# LoadSwitch.net
KiCad netlist of a schematic drawn in EAGLE
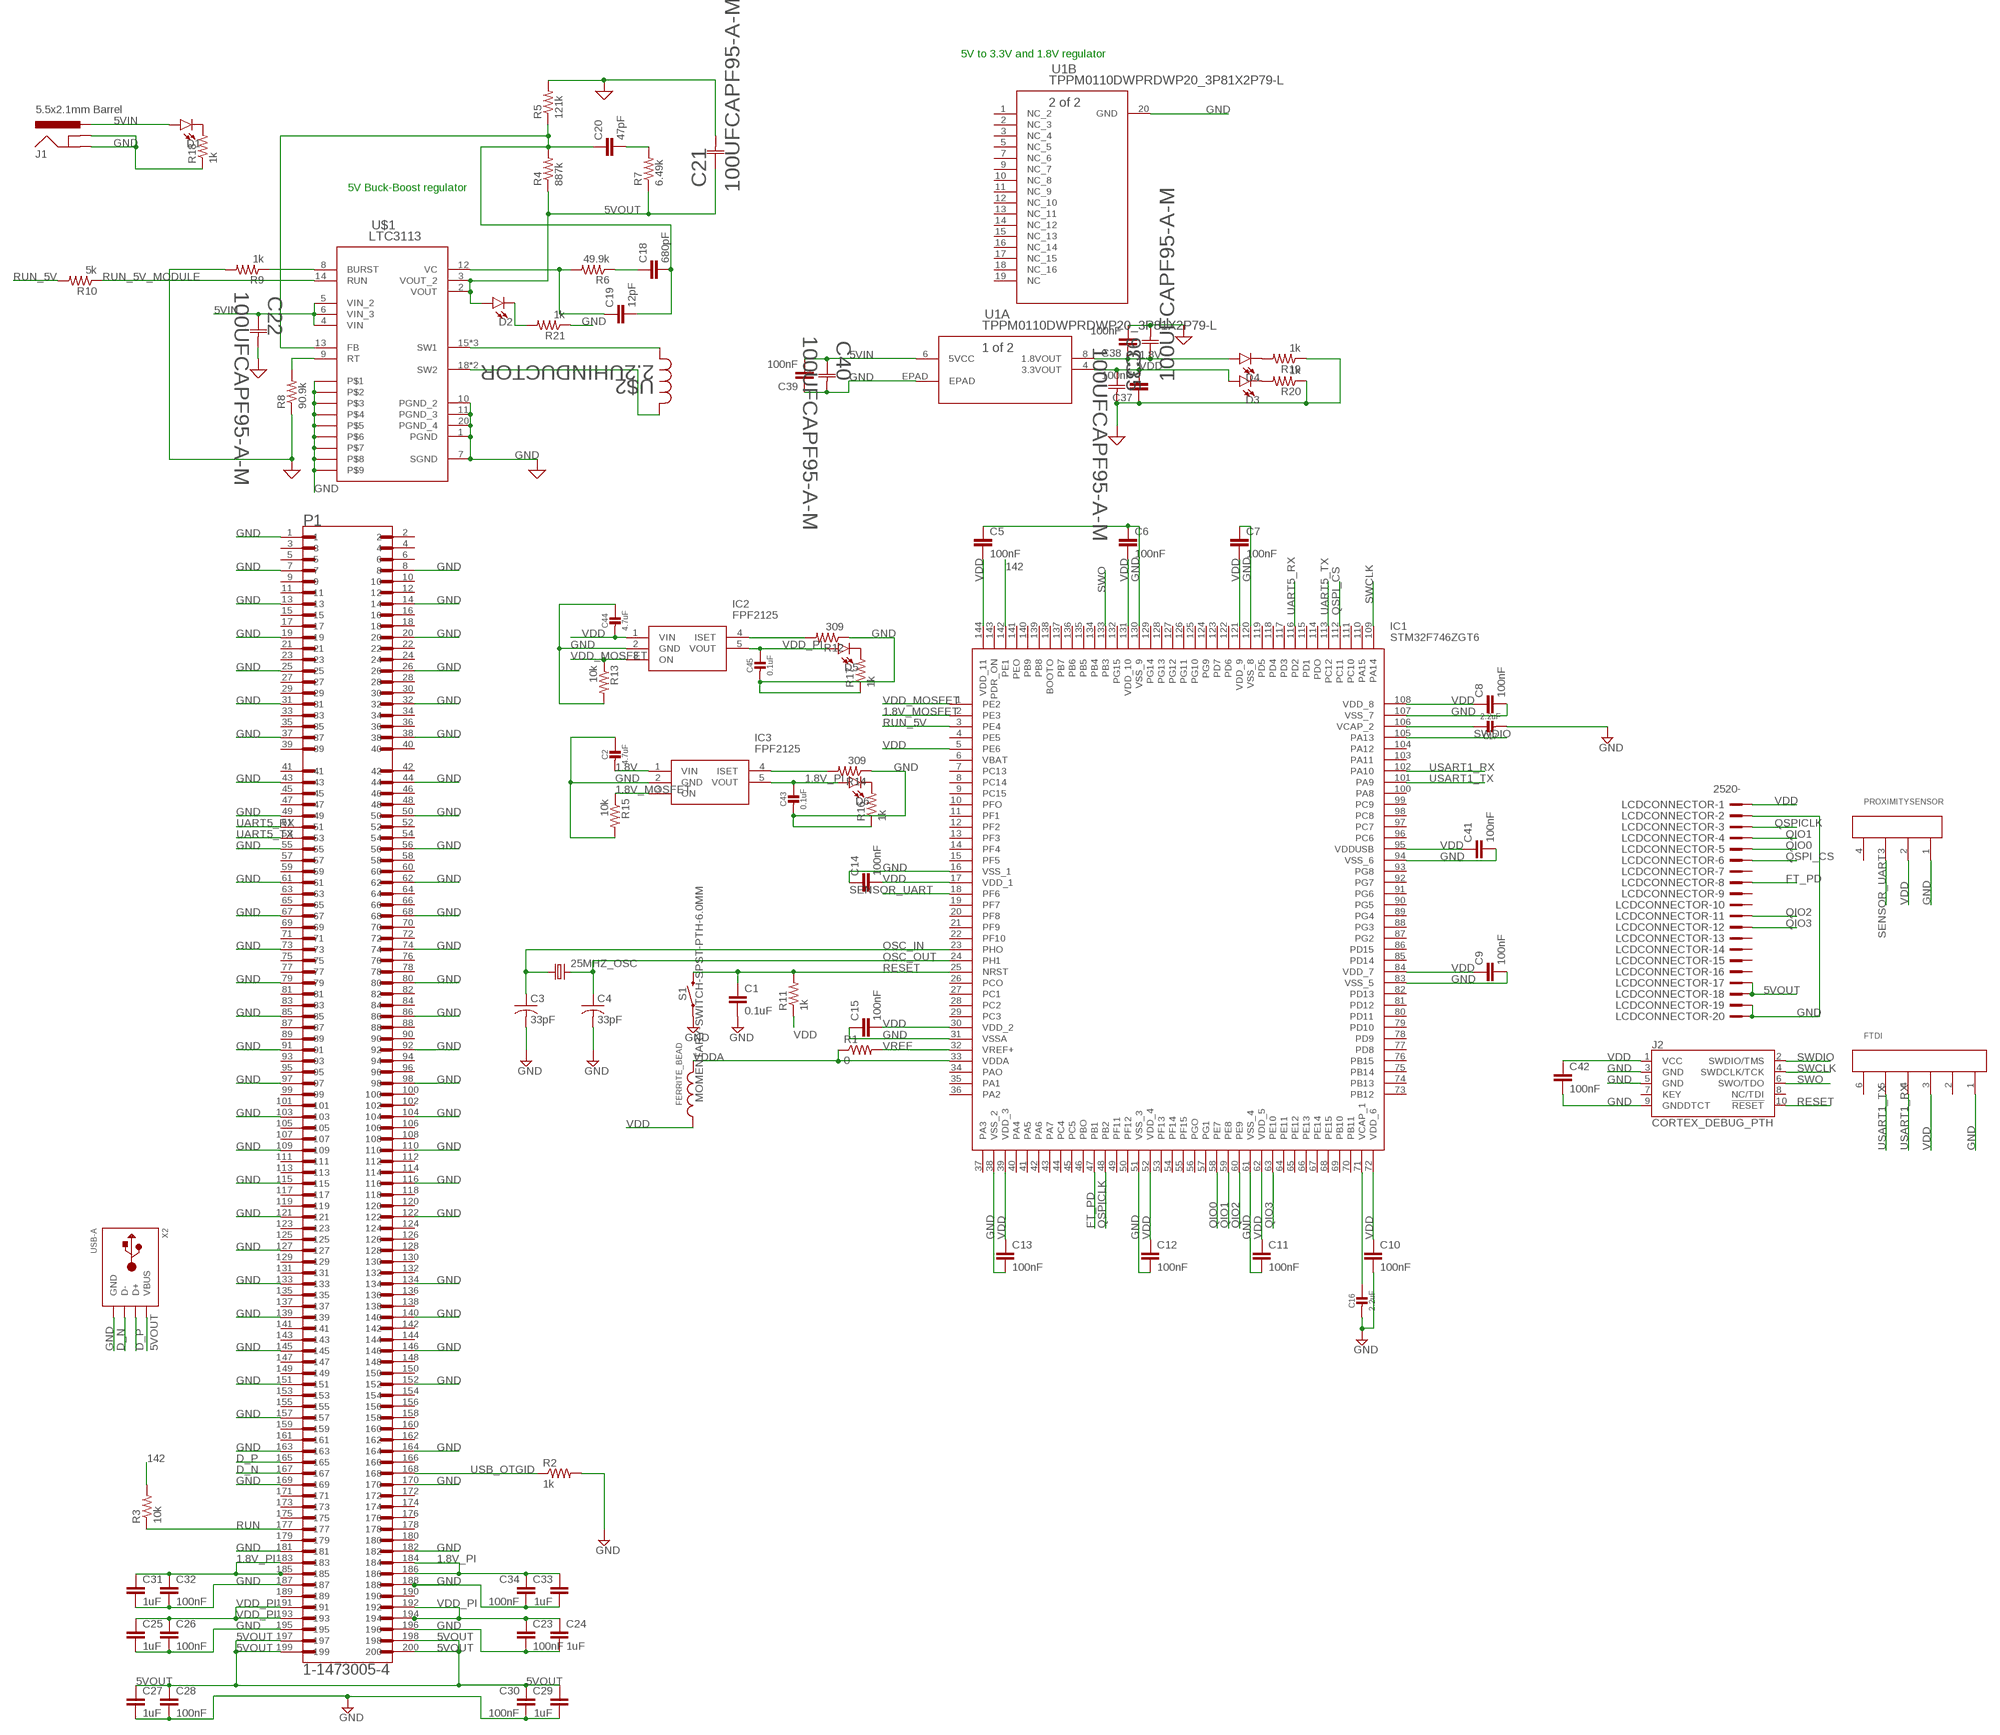
[diagram p0: schematic, sheet 1]

(export (version "E")
  (design (tool "Eeschema 10.0.6"))
  (components
    (comp (ref "25MHZ_OSC")
      (value "CRYSTALHC49UP")
      (footprint "eagle-import:HC49UP")
      (libsource (lib "eagle-import") (part "CRYSTALHC49UP"))
    )
    (comp (ref "C1")
      (value "0.1uF")
      (footprint "eagle-import:C0805")
      (libsource (lib "eagle-import") (part "C-EUC0805"))
    )
    (comp (ref "C2")
      (value "4.7uF")
      (footprint "eagle-import:0805-NO")
      (libsource (lib "eagle-import") (part "CAP_CERAMIC0805-NOOUTLINE"))
    )
    (comp (ref "C3")
      (value "33pF")
      (footprint "eagle-import:C0805")
      (libsource (lib "eagle-import") (part "C-USC0805"))
    )
    (comp (ref "C4")
      (value "33pF")
      (footprint "eagle-import:C0805")
      (libsource (lib "eagle-import") (part "C-USC0805"))
    )
    (comp (ref "C5")
      (value "100nF")
      (footprint "eagle-import:C0805")
      (libsource (lib "eagle-import") (part "C-EUC0805"))
    )
    (comp (ref "C6")
      (value "100nF")
      (footprint "eagle-import:C0805")
      (libsource (lib "eagle-import") (part "C-EUC0805"))
    )
    (comp (ref "C7")
      (value "100nF")
      (footprint "eagle-import:C0805")
      (libsource (lib "eagle-import") (part "C-EUC0805"))
    )
    (comp (ref "C8")
      (value "100nF")
      (footprint "eagle-import:C0805")
      (libsource (lib "eagle-import") (part "C-EUC0805"))
    )
    (comp (ref "C9")
      (value "100nF")
      (footprint "eagle-import:C0805")
      (libsource (lib "eagle-import") (part "C-EUC0805"))
    )
    (comp (ref "C10")
      (value "100nF")
      (footprint "eagle-import:C0805")
      (libsource (lib "eagle-import") (part "C-EUC0805"))
    )
    (comp (ref "C11")
      (value "100nF")
      (footprint "eagle-import:C0805")
      (libsource (lib "eagle-import") (part "C-EUC0805"))
    )
    (comp (ref "C12")
      (value "100nF")
      (footprint "eagle-import:C0805")
      (libsource (lib "eagle-import") (part "C-EUC0805"))
    )
    (comp (ref "C13")
      (value "100nF")
      (footprint "eagle-import:C0805")
      (libsource (lib "eagle-import") (part "C-EUC0805"))
    )
    (comp (ref "C14")
      (value "100nF")
      (footprint "eagle-import:C0805")
      (libsource (lib "eagle-import") (part "C-EUC0805"))
    )
    (comp (ref "C15")
      (value "100nF")
      (footprint "eagle-import:C0805")
      (libsource (lib "eagle-import") (part "C-EUC0805"))
    )
    (comp (ref "C16")
      (value "2.2uF")
      (footprint "eagle-import:0805-NO")
      (libsource (lib "eagle-import") (part "audio amplifier example_970892_CAP_CERAMIC0805-NOOUTLINE"))
    )
    (comp (ref "C17")
      (value "2.2uF")
      (footprint "eagle-import:0805-NO")
      (libsource (lib "eagle-import") (part "audio amplifier example_970892_CAP_CERAMIC0805-NOOUTLINE"))
    )
    (comp (ref "C18")
      (value "680pF")
      (footprint "eagle-import:C0805")
      (libsource (lib "eagle-import") (part "C-EUC0805"))
    )
    (comp (ref "C19")
      (value "12pF")
      (footprint "eagle-import:C0805")
      (libsource (lib "eagle-import") (part "C-EUC0805"))
    )
    (comp (ref "C20")
      (value "47pF")
      (footprint "eagle-import:C0805")
      (libsource (lib "eagle-import") (part "C-EUC0805"))
    )
    (comp (ref "C21")
      (value "100UFCAPF95-A-M")
      (footprint "eagle-import:F95-A-M")
      (fields (field (name "MANUFACTURER_PART_NUMBER") "F951A107KAAAQ2"))
      (libsource (lib "eagle-import") (part "100UFCAPF95-A-M"))
    )
    (comp (ref "C22")
      (value "100UFCAPF95-A-M")
      (footprint "eagle-import:F95-A-M")
      (fields (field (name "MANUFACTURER_PART_NUMBER") "F951A107KAAAQ2"))
      (libsource (lib "eagle-import") (part "100UFCAPF95-A-M"))
    )
    (comp (ref "C23")
      (value "100nF")
      (footprint "eagle-import:C0805")
      (libsource (lib "eagle-import") (part "C-EUC0805"))
    )
    (comp (ref "C24")
      (value "1uF")
      (footprint "eagle-import:C0805")
      (libsource (lib "eagle-import") (part "C-EUC0805"))
    )
    (comp (ref "C25")
      (value "1uF")
      (footprint "eagle-import:C0805")
      (libsource (lib "eagle-import") (part "C-EUC0805"))
    )
    (comp (ref "C26")
      (value "100nF")
      (footprint "eagle-import:C0805")
      (libsource (lib "eagle-import") (part "C-EUC0805"))
    )
    (comp (ref "C27")
      (value "1uF")
      (footprint "eagle-import:C0805")
      (libsource (lib "eagle-import") (part "C-EUC0805"))
    )
    (comp (ref "C28")
      (value "100nF")
      (footprint "eagle-import:C0805")
      (libsource (lib "eagle-import") (part "C-EUC0805"))
    )
    (comp (ref "C29")
      (value "1uF")
      (footprint "eagle-import:C0805")
      (libsource (lib "eagle-import") (part "C-EUC0805"))
    )
    (comp (ref "C30")
      (value "100nF")
      (footprint "eagle-import:C0805")
      (libsource (lib "eagle-import") (part "C-EUC0805"))
    )
    (comp (ref "C31")
      (value "1uF")
      (footprint "eagle-import:C0805")
      (libsource (lib "eagle-import") (part "C-EUC0805"))
    )
    (comp (ref "C32")
      (value "100nF")
      (footprint "eagle-import:C0805")
      (libsource (lib "eagle-import") (part "C-EUC0805"))
    )
    (comp (ref "C33")
      (value "1uF")
      (footprint "eagle-import:C0805")
      (libsource (lib "eagle-import") (part "C-EUC0805"))
    )
    (comp (ref "C34")
      (value "100nF")
      (footprint "eagle-import:C0805")
      (libsource (lib "eagle-import") (part "C-EUC0805"))
    )
    (comp (ref "C35")
      (value "100UFCAPF95-A-M")
      (footprint "eagle-import:F95-A-M")
      (fields (field (name "MANUFACTURER_PART_NUMBER") "F951A107KAAAQ2"))
      (libsource (lib "eagle-import") (part "100UFCAPF95-A-M"))
    )
    (comp (ref "C36")
      (value "100UFCAPF95-A-M")
      (footprint "eagle-import:F95-A-M")
      (fields (field (name "MANUFACTURER_PART_NUMBER") "F951A107KAAAQ2"))
      (libsource (lib "eagle-import") (part "100UFCAPF95-A-M"))
    )
    (comp (ref "C37")
      (value "100nF")
      (footprint "eagle-import:C0805")
      (libsource (lib "eagle-import") (part "C-EUC0805"))
    )
    (comp (ref "C38")
      (value "100nF")
      (footprint "eagle-import:C0805")
      (libsource (lib "eagle-import") (part "C-EUC0805"))
    )
    (comp (ref "C39")
      (value "100nF")
      (footprint "eagle-import:C0805")
      (libsource (lib "eagle-import") (part "C-EUC0805"))
    )
    (comp (ref "C40")
      (value "100UFCAPF95-A-M")
      (footprint "eagle-import:F95-A-M")
      (fields (field (name "MANUFACTURER_PART_NUMBER") "F951A107KAAAQ2"))
      (libsource (lib "eagle-import") (part "100UFCAPF95-A-M"))
    )
    (comp (ref "C41")
      (value "100nF")
      (footprint "eagle-import:C0805")
      (libsource (lib "eagle-import") (part "C-EUC0805"))
    )
    (comp (ref "C42")
      (value "100nF")
      (footprint "eagle-import:C0805")
      (libsource (lib "eagle-import") (part "C-EUC0805"))
    )
    (comp (ref "C43")
      (value "0.1uF")
      (footprint "eagle-import:0805-NO")
      (libsource (lib "eagle-import") (part "CAP_CERAMIC0805-NOOUTLINE"))
    )
    (comp (ref "C44")
      (value "4.7uF")
      (footprint "eagle-import:0805-NO")
      (libsource (lib "eagle-import") (part "CAP_CERAMIC0805-NOOUTLINE"))
    )
    (comp (ref "C45")
      (value "0.1uF")
      (footprint "eagle-import:0805-NO")
      (libsource (lib "eagle-import") (part "CAP_CERAMIC0805-NOOUTLINE"))
    )
    (comp (ref "D1")
      (value "LED0603")
      (footprint "eagle-import:LED-0603")
      (libsource (lib "eagle-import") (part "LED0603"))
    )
    (comp (ref "D2")
      (value "LED0603")
      (footprint "eagle-import:LED-0603")
      (libsource (lib "eagle-import") (part "LED0603"))
    )
    (comp (ref "D3")
      (value "LED0603")
      (footprint "eagle-import:LED-0603")
      (libsource (lib "eagle-import") (part "LED0603"))
    )
    (comp (ref "D4")
      (value "LED0603")
      (footprint "eagle-import:LED-0603")
      (libsource (lib "eagle-import") (part "LED0603"))
    )
    (comp (ref "D5")
      (value "LED0603")
      (footprint "eagle-import:LED-0603")
      (libsource (lib "eagle-import") (part "LED0603"))
    )
    (comp (ref "D6")
      (value "LED0603")
      (footprint "eagle-import:LED-0603")
      (libsource (lib "eagle-import") (part "LED0603"))
    )
    (comp (ref "FERRITE_BEAD")
      (value "WE-CBA_0805_782853112_HC")
      (footprint "eagle-import:WE-CBA_0805(W=4)")
      (libsource (lib "eagle-import") (part "WE-CBA_0805_HC_782853112"))
    )
    (comp (ref "FTDI")
      (value "66100611622")
      (footprint "eagle-import:66100611622")
      (libsource (lib "eagle-import") (part "66100611622"))
    )
    (comp (ref "IC1")
      (value "STM32F746ZGT6")
      (footprint "eagle-import:QFP50P2200X2200X160-144N")
      (fields
        (field (name "MOUSER_PART_NUMBER") "511-STM32F746ZGT6")
        (field (name "RS_PART_NUMBER") "8820290")
      )
      (libsource (lib "eagle-import") (part "STM32F746ZGT6"))
    )
    (comp (ref "IC2")
      (value "FPF2125")
      (footprint "eagle-import:SOT95P280X140-5N")
      (fields (field (name "MOUSER_PART_NUMBER") "512-FPF2125") (field (name "RS_PART_NUMBER") "7390195"))
      (libsource (lib "eagle-import") (part "FPF2125"))
    )
    (comp (ref "IC3")
      (value "FPF2125")
      (footprint "eagle-import:SOT95P280X140-5N")
      (fields (field (name "MOUSER_PART_NUMBER") "512-FPF2125") (field (name "RS_PART_NUMBER") "7390195"))
      (libsource (lib "eagle-import") (part "FPF2125"))
    )
    (comp (ref "J1")
      (value "5.5x2.1mm Barrel")
      (footprint "eagle-import:POWER_JACK_SMD")
      (libsource (lib "eagle-import") (part "POWER_JACKSMD"))
    )
    (comp (ref "J2")
      (value "CORTEX_DEBUG_PTH")
      (footprint "eagle-import:2X5-PTH-1.27MM")
      (libsource (lib "eagle-import") (part "CORTEX_DEBUG_PTH"))
    )
    (comp (ref "LCDCONNECTOR")
      (value "2520-")
      (footprint "eagle-import:PAK100_2500-20")
      (libsource (lib "eagle-import") (part "2520-"))
    )
    (comp (ref "P1")
      (value "1-1473005-4")
      (footprint "eagle-import:TE_1-1473005-4")
      (fields (field (name "MF") "TE Connectivity"))
      (libsource (lib "eagle-import") (part "1-1473005-4"))
    )
    (comp (ref "PROXIMITYSENSOR")
      (value "66100411622")
      (footprint "eagle-import:66100411622")
      (libsource (lib "eagle-import") (part "66100411622"))
    )
    (comp (ref "R1")
      (value "0")
      (footprint "eagle-import:R0805")
      (libsource (lib "eagle-import") (part "R-US_R0805"))
    )
    (comp (ref "R2")
      (value "1k")
      (footprint "eagle-import:R0805")
      (libsource (lib "eagle-import") (part "R-US_R0805"))
    )
    (comp (ref "R3")
      (value "10k")
      (footprint "eagle-import:R0805")
      (libsource (lib "eagle-import") (part "R-US_R0805"))
    )
    (comp (ref "R4")
      (value "887k")
      (footprint "eagle-import:R0805")
      (libsource (lib "eagle-import") (part "resistor_348_R-US_R0805"))
    )
    (comp (ref "R5")
      (value "121k")
      (footprint "eagle-import:R0805")
      (libsource (lib "eagle-import") (part "resistor_348_R-US_R0805"))
    )
    (comp (ref "R6")
      (value "49.9k")
      (footprint "eagle-import:R0805")
      (libsource (lib "eagle-import") (part "resistor_348_R-US_R0805"))
    )
    (comp (ref "R7")
      (value "6.49k")
      (footprint "eagle-import:R0805")
      (libsource (lib "eagle-import") (part "resistor_348_R-US_R0805"))
    )
    (comp (ref "R8")
      (value "90.9k")
      (footprint "eagle-import:R0805")
      (libsource (lib "eagle-import") (part "resistor_348_R-US_R0805"))
    )
    (comp (ref "R9")
      (value "1k")
      (footprint "eagle-import:R0805")
      (libsource (lib "eagle-import") (part "resistor_348_R-US_R0805"))
    )
    (comp (ref "R10")
      (value "5k")
      (footprint "eagle-import:R0805")
      (libsource (lib "eagle-import") (part "resistor_348_R-US_R0805"))
    )
    (comp (ref "R11")
      (value "1k")
      (footprint "eagle-import:R0805")
      (libsource (lib "eagle-import") (part "R-US_R0805"))
    )
    (comp (ref "R12")
      (value "309")
      (footprint "eagle-import:R0805")
      (libsource (lib "eagle-import") (part "R-US_R0805"))
    )
    (comp (ref "R13")
      (value "10k")
      (footprint "eagle-import:R0805")
      (libsource (lib "eagle-import") (part "R-US_R0805"))
    )
    (comp (ref "R14")
      (value "309")
      (footprint "eagle-import:R0805")
      (libsource (lib "eagle-import") (part "R-US_R0805"))
    )
    (comp (ref "R15")
      (value "10k")
      (footprint "eagle-import:R0805")
      (libsource (lib "eagle-import") (part "R-US_R0805"))
    )
    (comp (ref "R16")
      (value "1k")
      (footprint "eagle-import:R0805")
      (libsource (lib "eagle-import") (part "R-US_R0805"))
    )
    (comp (ref "R17")
      (value "1k")
      (footprint "eagle-import:R0805")
      (libsource (lib "eagle-import") (part "R-US_R0805"))
    )
    (comp (ref "R18")
      (value "1k")
      (footprint "eagle-import:R0805")
      (libsource (lib "eagle-import") (part "R-US_R0805"))
    )
    (comp (ref "R19")
      (value "1k")
      (footprint "eagle-import:R0805")
      (libsource (lib "eagle-import") (part "R-US_R0805"))
    )
    (comp (ref "R20")
      (value "1k")
      (footprint "eagle-import:R0805")
      (libsource (lib "eagle-import") (part "R-US_R0805"))
    )
    (comp (ref "R21")
      (value "1k")
      (footprint "eagle-import:R0805")
      (libsource (lib "eagle-import") (part "R-US_R0805"))
    )
    (comp (ref "S1")
      (value "MOMENTARY-SWITCH-SPST-PTH-6.0MM")
      (footprint "eagle-import:TACTILE_SWITCH_PTH_6.0MM")
      (libsource (lib "eagle-import") (part "MOMENTARY-SWITCH-SPST-PTH-6.0MM"))
    )
    (comp (ref "U$1")
      (value "LTC3113")
      (footprint "eagle-import:TSSOP-20_FE_CA")
      (libsource (lib "eagle-import") (part "LTC3113"))
    )
    (comp (ref "U$2")
      (value "2.2UHINDUCTOR")
      (footprint "eagle-import:IND_10040")
      (libsource (lib "eagle-import") (part "2.2UHINDUCTOR"))
    )
    (comp (ref "U1")
      (value "TPPM0110DWPRDWP20_3P81X2P79-L")
      (footprint "eagle-import:DWP20_3P81X2P79-L")
      (fields (field (name "MANUFACTURER_PART_NUMBER") "TPPM0110DWPR"))
      (libsource (lib "eagle-import") (part "TPPM0110DWPRDWP20_3P81X2P79-L"))
    )
    (comp (ref "X2")
      (value "USB-A")
      (footprint "eagle-import:MOLEX_480371000")
      (libsource (lib "eagle-import") (part "USB-A"))
    )
  )
  (nets
    (net (code "1") (name "/1.8V") (class "Default")
      (node (ref "C2") (pin "2") (pinfunction "2_2") (pintype "passive"))
      (node (ref "C36") (pin "1") (pinfunction "1_1") (pintype "passive"))
      (node (ref "C38") (pin "1") (pinfunction "1_1") (pintype "passive"))
      (node (ref "D4") (pin "A") (pinfunction "A_A") (pintype "passive"))
      (node (ref "IC3") (pin "1") (pinfunction "VIN_1") (pintype "input"))
      (node (ref "U1") (pin "8") (pinfunction "1.8VOUT_8") (pintype "output"))
    )
    (net (code "2") (name "/1.8V_MOSFET") (class "Default")
      (node (ref "IC1") (pin "2") (pinfunction "PE3_2") (pintype "bidirectional"))
      (node (ref "IC3") (pin "3") (pinfunction "ON_3") (pintype "input"))
      (node (ref "R15") (pin "1") (pinfunction "1_1") (pintype "passive"))
    )
    (net (code "3") (name "/1.8V_PI") (class "Default")
      (node (ref "C31") (pin "1") (pinfunction "1_1") (pintype "passive"))
      (node (ref "C32") (pin "1") (pinfunction "1_1") (pintype "passive"))
      (node (ref "C33") (pin "1") (pinfunction "1_1") (pintype "passive"))
      (node (ref "C34") (pin "1") (pinfunction "1_1") (pintype "passive"))
      (node (ref "C43") (pin "1") (pinfunction "1_1") (pintype "passive"))
      (node (ref "D6") (pin "A") (pinfunction "A_A") (pintype "passive"))
      (node (ref "IC3") (pin "5") (pinfunction "VOUT_5") (pintype "output"))
      (node (ref "P1") (pin "183") (pinfunction "183_183") (pintype "passive"))
      (node (ref "P1") (pin "184") (pinfunction "184_184") (pintype "passive"))
      (node (ref "P1") (pin "185") (pinfunction "185_185") (pintype "passive"))
      (node (ref "P1") (pin "186") (pinfunction "186_186") (pintype "passive"))
    )
    (net (code "4") (name "/5VIN") (class "Default")
      (node (ref "C22") (pin "1") (pinfunction "1_1") (pintype "passive"))
      (node (ref "C39") (pin "2") (pinfunction "2_2") (pintype "passive"))
      (node (ref "C40") (pin "1") (pinfunction "1_1") (pintype "passive"))
      (node (ref "D1") (pin "A") (pinfunction "A_A") (pintype "passive"))
      (node (ref "J1") (pin "VIN0") (pinfunction "PWR_VIN0") (pintype "bidirectional"))
      (node (ref "U$1") (pin "4") (pinfunction "VIN_4") (pintype "passive"))
      (node (ref "U$1") (pin "5") (pinfunction "VIN_2_5") (pintype "passive"))
      (node (ref "U$1") (pin "6") (pinfunction "VIN_3_6") (pintype "passive"))
      (node (ref "U1") (pin "6") (pinfunction "5VCC_6") (pintype "input"))
    )
    (net (code "5") (name "/5VOUT") (class "Default")
      (node (ref "C21") (pin "1") (pinfunction "1_1") (pintype "passive"))
      (node (ref "C27") (pin "1") (pinfunction "1_1") (pintype "passive"))
      (node (ref "C28") (pin "1") (pinfunction "1_1") (pintype "passive"))
      (node (ref "C29") (pin "1") (pinfunction "1_1") (pintype "passive"))
      (node (ref "C30") (pin "1") (pinfunction "1_1") (pintype "passive"))
      (node (ref "D2") (pin "A") (pinfunction "A_A") (pintype "passive"))
      (node (ref "LCDCONNECTOR") (pin "17") (pinfunction "KL_17") (pintype "passive"))
      (node (ref "LCDCONNECTOR") (pin "18") (pinfunction "KL_18") (pintype "passive"))
      (node (ref "P1") (pin "197") (pinfunction "197_197") (pintype "passive"))
      (node (ref "P1") (pin "198") (pinfunction "198_198") (pintype "passive"))
      (node (ref "P1") (pin "199") (pinfunction "199_199") (pintype "passive"))
      (node (ref "P1") (pin "200") (pinfunction "200_200") (pintype "passive"))
      (node (ref "R4") (pin "1") (pinfunction "1_1") (pintype "passive"))
      (node (ref "R7") (pin "1") (pinfunction "1_1") (pintype "passive"))
      (node (ref "U$1") (pin "2") (pinfunction "VOUT_2") (pintype "passive"))
      (node (ref "U$1") (pin "3") (pinfunction "VOUT_2_3") (pintype "passive"))
      (node (ref "X2") (pin "1") (pinfunction "VBUS_1") (pintype "power_in"))
    )
    (net (code "6") (name "/142") (class "Default")
      (node (ref "IC1") (pin "142") (pinfunction "PE1_142") (pintype "bidirectional"))
      (node (ref "R3") (pin "2") (pinfunction "2_2") (pintype "passive"))
    )
    (net (code "7") (name "/D_N") (class "Default")
      (node (ref "P1") (pin "167") (pinfunction "167_167") (pintype "passive"))
      (node (ref "X2") (pin "2") (pinfunction "D-_2") (pintype "bidirectional"))
    )
    (net (code "8") (name "/D_P") (class "Default")
      (node (ref "P1") (pin "165") (pinfunction "165_165") (pintype "passive"))
      (node (ref "X2") (pin "3") (pinfunction "D+_3") (pintype "bidirectional"))
    )
    (net (code "9") (name "/FT_PD") (class "Default")
      (node (ref "IC1") (pin "47") (pinfunction "PB1_47") (pintype "bidirectional"))
      (node (ref "LCDCONNECTOR") (pin "8") (pinfunction "KL_8") (pintype "passive"))
    )
    (net (code "10") (name "/OSC_IN") (class "Default")
      (node (ref "25MHZ_OSC") (pin "1") (pinfunction "1_1") (pintype "passive"))
      (node (ref "C3") (pin "1") (pinfunction "1_1") (pintype "passive"))
      (node (ref "IC1") (pin "23") (pinfunction "PHO_23") (pintype "bidirectional"))
    )
    (net (code "11") (name "/OSC_OUT") (class "Default")
      (node (ref "25MHZ_OSC") (pin "2") (pinfunction "2_2") (pintype "passive"))
      (node (ref "C4") (pin "1") (pinfunction "1_1") (pintype "passive"))
      (node (ref "IC1") (pin "24") (pinfunction "PH1_24") (pintype "bidirectional"))
    )
    (net (code "12") (name "/QIO0") (class "Default")
      (node (ref "IC1") (pin "58") (pinfunction "PE7_58") (pintype "bidirectional"))
      (node (ref "LCDCONNECTOR") (pin "5") (pinfunction "KL_5") (pintype "passive"))
    )
    (net (code "13") (name "/QIO1") (class "Default")
      (node (ref "IC1") (pin "59") (pinfunction "PE8_59") (pintype "bidirectional"))
      (node (ref "LCDCONNECTOR") (pin "4") (pinfunction "KL_4") (pintype "passive"))
    )
    (net (code "14") (name "/QIO2") (class "Default")
      (node (ref "IC1") (pin "60") (pinfunction "PE9_60") (pintype "bidirectional"))
      (node (ref "LCDCONNECTOR") (pin "11") (pinfunction "KL_11") (pintype "passive"))
    )
    (net (code "15") (name "/QIO3") (class "Default")
      (node (ref "IC1") (pin "63") (pinfunction "PE10_63") (pintype "bidirectional"))
      (node (ref "LCDCONNECTOR") (pin "12") (pinfunction "KL_12") (pintype "passive"))
    )
    (net (code "16") (name "/QSPICLK") (class "Default")
      (node (ref "IC1") (pin "48") (pinfunction "PB2_48") (pintype "bidirectional"))
      (node (ref "LCDCONNECTOR") (pin "3") (pinfunction "KL_3") (pintype "passive"))
    )
    (net (code "17") (name "/QSPI_CS") (class "Default")
      (node (ref "IC1") (pin "112") (pinfunction "PC11_112") (pintype "bidirectional"))
      (node (ref "LCDCONNECTOR") (pin "6") (pinfunction "KL_6") (pintype "passive"))
    )
    (net (code "18") (name "/RESET") (class "Default")
      (node (ref "C1") (pin "1") (pinfunction "1_1") (pintype "passive"))
      (node (ref "IC1") (pin "25") (pinfunction "NRST_25") (pintype "input"))
      (node (ref "J2") (pin "10") (pinfunction "~{RESET}_10") (pintype "bidirectional"))
      (node (ref "R11") (pin "2") (pinfunction "2_2") (pintype "passive"))
      (node (ref "S1") (pin "3") (pinfunction "2_3") (pintype "passive"))
    )
    (net (code "19") (name "/RUN") (class "Default")
      (node (ref "P1") (pin "177") (pinfunction "177_177") (pintype "passive"))
      (node (ref "R3") (pin "1") (pinfunction "1_1") (pintype "passive"))
    )
    (net (code "20") (name "/RUN_5V") (class "Default")
      (node (ref "IC1") (pin "3") (pinfunction "PE4_3") (pintype "bidirectional"))
      (node (ref "R10") (pin "2") (pinfunction "2_2") (pintype "passive"))
    )
    (net (code "21") (name "/RUN_5V_MODULE") (class "Default")
      (node (ref "R10") (pin "1") (pinfunction "1_1") (pintype "passive"))
      (node (ref "U$1") (pin "14") (pinfunction "RUN_14") (pintype "passive"))
    )
    (net (code "22") (name "/SENSOR_UART") (class "Default")
      (node (ref "IC1") (pin "18") (pinfunction "PF6_18") (pintype "bidirectional"))
      (node (ref "PROXIMITYSENSOR") (pin "3") (pinfunction "3_3") (pintype "passive"))
    )
    (net (code "23") (name "/SWCLK") (class "Default")
      (node (ref "IC1") (pin "109") (pinfunction "PA14_109") (pintype "bidirectional"))
      (node (ref "J2") (pin "4") (pinfunction "SWDCLK/TCK_4") (pintype "bidirectional"))
    )
    (net (code "24") (name "/SWDIO") (class "Default")
      (node (ref "IC1") (pin "105") (pinfunction "PA13_105") (pintype "bidirectional"))
      (node (ref "J2") (pin "2") (pinfunction "SWDIO/TMS_2") (pintype "bidirectional"))
    )
    (net (code "25") (name "/SWO") (class "Default")
      (node (ref "IC1") (pin "133") (pinfunction "PB3_133") (pintype "bidirectional"))
      (node (ref "J2") (pin "6") (pinfunction "SWO/TDO_6") (pintype "bidirectional"))
    )
    (net (code "26") (name "/UART5_RX") (class "Default")
      (node (ref "IC1") (pin "116") (pinfunction "PD2_116") (pintype "bidirectional"))
      (node (ref "P1") (pin "51") (pinfunction "51_51") (pintype "passive"))
    )
    (net (code "27") (name "/UART5_TX") (class "Default")
      (node (ref "IC1") (pin "113") (pinfunction "PC12_113") (pintype "bidirectional"))
      (node (ref "P1") (pin "53") (pinfunction "53_53") (pintype "passive"))
    )
    (net (code "28") (name "/USART1_RX") (class "Default")
      (node (ref "FTDI") (pin "4") (pinfunction "4_4") (pintype "passive"))
      (node (ref "IC1") (pin "102") (pinfunction "PA10_102") (pintype "bidirectional"))
    )
    (net (code "29") (name "/USART1_TX") (class "Default")
      (node (ref "FTDI") (pin "5") (pinfunction "5_5") (pintype "passive"))
      (node (ref "IC1") (pin "101") (pinfunction "PA9_101") (pintype "bidirectional"))
    )
    (net (code "30") (name "/USB_OTGID") (class "Default")
      (node (ref "P1") (pin "168") (pinfunction "168_168") (pintype "passive"))
      (node (ref "R2") (pin "1") (pinfunction "1_1") (pintype "passive"))
    )
    (net (code "31") (name "/VDD") (class "Default")
      (node (ref "C10") (pin "1") (pinfunction "1_1") (pintype "passive"))
      (node (ref "C11") (pin "1") (pinfunction "1_1") (pintype "passive"))
      (node (ref "C12") (pin "1") (pinfunction "1_1") (pintype "passive"))
      (node (ref "C13") (pin "1") (pinfunction "1_1") (pintype "passive"))
      (node (ref "C14") (pin "2") (pinfunction "2_2") (pintype "passive"))
      (node (ref "C15") (pin "2") (pinfunction "2_2") (pintype "passive"))
      (node (ref "C35") (pin "1") (pinfunction "1_1") (pintype "passive"))
      (node (ref "C37") (pin "2") (pinfunction "2_2") (pintype "passive"))
      (node (ref "C41") (pin "1") (pinfunction "1_1") (pintype "passive"))
      (node (ref "C42") (pin "1") (pinfunction "1_1") (pintype "passive"))
      (node (ref "C44") (pin "2") (pinfunction "2_2") (pintype "passive"))
      (node (ref "C5") (pin "2") (pinfunction "2_2") (pintype "passive"))
      (node (ref "C6") (pin "2") (pinfunction "2_2") (pintype "passive"))
      (node (ref "C7") (pin "2") (pinfunction "2_2") (pintype "passive"))
      (node (ref "C8") (pin "1") (pinfunction "1_1") (pintype "passive"))
      (node (ref "C9") (pin "1") (pinfunction "1_1") (pintype "passive"))
      (node (ref "D3") (pin "A") (pinfunction "A_A") (pintype "passive"))
      (node (ref "FERRITE_BEAD") (pin "1") (pinfunction "1_1") (pintype "passive"))
      (node (ref "FTDI") (pin "3") (pinfunction "3_3") (pintype "passive"))
      (node (ref "IC1") (pin "108") (pinfunction "VDD_8_108") (pintype "power_in"))
      (node (ref "IC1") (pin "121") (pinfunction "VDD_9_121") (pintype "power_in"))
      (node (ref "IC1") (pin "131") (pinfunction "VDD_10_131") (pintype "power_in"))
      (node (ref "IC1") (pin "144") (pinfunction "VDD_11_144") (pintype "power_in"))
      (node (ref "IC1") (pin "17") (pinfunction "VDD_1_17") (pintype "power_in"))
      (node (ref "IC1") (pin "30") (pinfunction "VDD_2_30") (pintype "power_in"))
      (node (ref "IC1") (pin "39") (pinfunction "VDD_3_39") (pintype "power_in"))
      (node (ref "IC1") (pin "5") (pinfunction "PE6_5") (pintype "bidirectional"))
      (node (ref "IC1") (pin "52") (pinfunction "VDD_4_52") (pintype "power_in"))
      (node (ref "IC1") (pin "62") (pinfunction "VDD_5_62") (pintype "power_in"))
      (node (ref "IC1") (pin "72") (pinfunction "VDD_6_72") (pintype "power_in"))
      (node (ref "IC1") (pin "84") (pinfunction "VDD_7_84") (pintype "power_in"))
      (node (ref "IC1") (pin "95") (pinfunction "VDDUSB_95") (pintype "power_in"))
      (node (ref "IC2") (pin "1") (pinfunction "VIN_1") (pintype "input"))
      (node (ref "J2") (pin "1") (pinfunction "VCC_1") (pintype "bidirectional"))
      (node (ref "LCDCONNECTOR") (pin "1") (pinfunction "KL_1") (pintype "passive"))
      (node (ref "PROXIMITYSENSOR") (pin "2") (pinfunction "2_2") (pintype "passive"))
      (node (ref "R11") (pin "1") (pinfunction "1_1") (pintype "passive"))
      (node (ref "U1") (pin "4") (pinfunction "3.3VOUT_4") (pintype "output"))
    )
    (net (code "32") (name "/VDDA") (class "Default")
      (node (ref "FERRITE_BEAD") (pin "2") (pinfunction "2_2") (pintype "passive"))
      (node (ref "IC1") (pin "33") (pinfunction "VDDA_33") (pintype "power_in"))
      (node (ref "R1") (pin "1") (pinfunction "1_1") (pintype "passive"))
    )
    (net (code "33") (name "/VDD_MOSFET") (class "Default")
      (node (ref "IC1") (pin "1") (pinfunction "PE2_1") (pintype "bidirectional"))
      (node (ref "IC2") (pin "3") (pinfunction "ON_3") (pintype "input"))
      (node (ref "R13") (pin "1") (pinfunction "1_1") (pintype "passive"))
    )
    (net (code "34") (name "/VDD_PI") (class "Default")
      (node (ref "C23") (pin "1") (pinfunction "1_1") (pintype "passive"))
      (node (ref "C24") (pin "1") (pinfunction "1_1") (pintype "passive"))
      (node (ref "C25") (pin "1") (pinfunction "1_1") (pintype "passive"))
      (node (ref "C26") (pin "1") (pinfunction "1_1") (pintype "passive"))
      (node (ref "C45") (pin "1") (pinfunction "1_1") (pintype "passive"))
      (node (ref "D5") (pin "A") (pinfunction "A_A") (pintype "passive"))
      (node (ref "IC2") (pin "5") (pinfunction "VOUT_5") (pintype "output"))
      (node (ref "P1") (pin "191") (pinfunction "191_191") (pintype "passive"))
      (node (ref "P1") (pin "192") (pinfunction "192_192") (pintype "passive"))
      (node (ref "P1") (pin "193") (pinfunction "193_193") (pintype "passive"))
      (node (ref "P1") (pin "194") (pinfunction "194_194") (pintype "passive"))
    )
    (net (code "35") (name "/VREF") (class "Default")
      (node (ref "IC1") (pin "32") (pinfunction "VREF+_32") (pintype "input"))
      (node (ref "R1") (pin "2") (pinfunction "2_2") (pintype "passive"))
    )
    (net (code "36") (name "GND") (class "Default")
      (node (ref "C1") (pin "2") (pinfunction "2_2") (pintype "passive"))
      (node (ref "C10") (pin "2") (pinfunction "2_2") (pintype "passive"))
      (node (ref "C11") (pin "2") (pinfunction "2_2") (pintype "passive"))
      (node (ref "C12") (pin "2") (pinfunction "2_2") (pintype "passive"))
      (node (ref "C13") (pin "2") (pinfunction "2_2") (pintype "passive"))
      (node (ref "C14") (pin "1") (pinfunction "1_1") (pintype "passive"))
      (node (ref "C15") (pin "1") (pinfunction "1_1") (pintype "passive"))
      (node (ref "C16") (pin "2") (pinfunction "2_2") (pintype "passive"))
      (node (ref "C17") (pin "2") (pinfunction "2_2") (pintype "passive"))
      (node (ref "C2") (pin "1") (pinfunction "1_1") (pintype "passive"))
      (node (ref "C21") (pin "2") (pinfunction "2_2") (pintype "passive"))
      (node (ref "C22") (pin "2") (pinfunction "2_2") (pintype "passive"))
      (node (ref "C23") (pin "2") (pinfunction "2_2") (pintype "passive"))
      (node (ref "C24") (pin "2") (pinfunction "2_2") (pintype "passive"))
      (node (ref "C25") (pin "2") (pinfunction "2_2") (pintype "passive"))
      (node (ref "C26") (pin "2") (pinfunction "2_2") (pintype "passive"))
      (node (ref "C27") (pin "2") (pinfunction "2_2") (pintype "passive"))
      (node (ref "C28") (pin "2") (pinfunction "2_2") (pintype "passive"))
      (node (ref "C29") (pin "2") (pinfunction "2_2") (pintype "passive"))
      (node (ref "C3") (pin "2") (pinfunction "2_2") (pintype "passive"))
      (node (ref "C30") (pin "2") (pinfunction "2_2") (pintype "passive"))
      (node (ref "C31") (pin "2") (pinfunction "2_2") (pintype "passive"))
      (node (ref "C32") (pin "2") (pinfunction "2_2") (pintype "passive"))
      (node (ref "C33") (pin "2") (pinfunction "2_2") (pintype "passive"))
      (node (ref "C34") (pin "2") (pinfunction "2_2") (pintype "passive"))
      (node (ref "C35") (pin "2") (pinfunction "2_2") (pintype "passive"))
      (node (ref "C36") (pin "2") (pinfunction "2_2") (pintype "passive"))
      (node (ref "C37") (pin "1") (pinfunction "1_1") (pintype "passive"))
      (node (ref "C38") (pin "2") (pinfunction "2_2") (pintype "passive"))
      (node (ref "C39") (pin "1") (pinfunction "1_1") (pintype "passive"))
      (node (ref "C4") (pin "2") (pinfunction "2_2") (pintype "passive"))
      (node (ref "C40") (pin "2") (pinfunction "2_2") (pintype "passive"))
      (node (ref "C41") (pin "2") (pinfunction "2_2") (pintype "passive"))
      (node (ref "C42") (pin "2") (pinfunction "2_2") (pintype "passive"))
      (node (ref "C43") (pin "2") (pinfunction "2_2") (pintype "passive"))
      (node (ref "C44") (pin "1") (pinfunction "1_1") (pintype "passive"))
      (node (ref "C45") (pin "2") (pinfunction "2_2") (pintype "passive"))
      (node (ref "C5") (pin "1") (pinfunction "1_1") (pintype "passive"))
      (node (ref "C6") (pin "1") (pinfunction "1_1") (pintype "passive"))
      (node (ref "C7") (pin "1") (pinfunction "1_1") (pintype "passive"))
      (node (ref "C8") (pin "2") (pinfunction "2_2") (pintype "passive"))
      (node (ref "C9") (pin "2") (pinfunction "2_2") (pintype "passive"))
      (node (ref "FTDI") (pin "1") (pinfunction "1_1") (pintype "passive"))
      (node (ref "IC1") (pin "107") (pinfunction "VSS_7_107") (pintype "power_in"))
      (node (ref "IC1") (pin "120") (pinfunction "VSS_8_120") (pintype "power_in"))
      (node (ref "IC1") (pin "130") (pinfunction "VSS_9_130") (pintype "power_in"))
      (node (ref "IC1") (pin "16") (pinfunction "VSS_1_16") (pintype "power_in"))
      (node (ref "IC1") (pin "31") (pinfunction "VSSA_31") (pintype "power_in"))
      (node (ref "IC1") (pin "38") (pinfunction "VSS_2_38") (pintype "power_in"))
      (node (ref "IC1") (pin "51") (pinfunction "VSS_3_51") (pintype "power_in"))
      (node (ref "IC1") (pin "61") (pinfunction "VSS_4_61") (pintype "power_in"))
      (node (ref "IC1") (pin "83") (pinfunction "VSS_5_83") (pintype "power_in"))
      (node (ref "IC1") (pin "94") (pinfunction "VSS_6_94") (pintype "power_in"))
      (node (ref "IC2") (pin "2") (pinfunction "GND_2") (pintype "power_in"))
      (node (ref "IC3") (pin "2") (pinfunction "GND_2") (pintype "power_in"))
      (node (ref "J1") (pin "GND") (pinfunction "GNDBREAK_GND") (pintype "bidirectional"))
      (node (ref "J1") (pin "P$4") (pinfunction "GND_P$4") (pintype "bidirectional"))
      (node (ref "J2") (pin "3") (pinfunction "GND_3") (pintype "bidirectional"))
      (node (ref "J2") (pin "5") (pinfunction "GND_5") (pintype "bidirectional"))
      (node (ref "J2") (pin "9") (pinfunction "GNDDTCT_9") (pintype "bidirectional"))
      (node (ref "LCDCONNECTOR") (pin "19") (pinfunction "KL_19") (pintype "passive"))
      (node (ref "LCDCONNECTOR") (pin "2") (pinfunction "KL_2") (pintype "passive"))
      (node (ref "LCDCONNECTOR") (pin "20") (pinfunction "KL_20") (pintype "passive"))
      (node (ref "P1") (pin "1") (pinfunction "1_1") (pintype "passive"))
      (node (ref "P1") (pin "103") (pinfunction "103_103") (pintype "passive"))
      (node (ref "P1") (pin "104") (pinfunction "104_104") (pintype "passive"))
      (node (ref "P1") (pin "109") (pinfunction "109_109") (pintype "passive"))
      (node (ref "P1") (pin "110") (pinfunction "110_110") (pintype "passive"))
      (node (ref "P1") (pin "115") (pinfunction "115_115") (pintype "passive"))
      (node (ref "P1") (pin "116") (pinfunction "116_116") (pintype "passive"))
      (node (ref "P1") (pin "121") (pinfunction "121_121") (pintype "passive"))
      (node (ref "P1") (pin "122") (pinfunction "122_122") (pintype "passive"))
      (node (ref "P1") (pin "127") (pinfunction "127_127") (pintype "passive"))
      (node (ref "P1") (pin "13") (pinfunction "13_13") (pintype "passive"))
      (node (ref "P1") (pin "133") (pinfunction "133_133") (pintype "passive"))
      (node (ref "P1") (pin "134") (pinfunction "134_134") (pintype "passive"))
      (node (ref "P1") (pin "139") (pinfunction "139_139") (pintype "passive"))
      (node (ref "P1") (pin "14") (pinfunction "14_14") (pintype "passive"))
      (node (ref "P1") (pin "140") (pinfunction "140_140") (pintype "passive"))
      (node (ref "P1") (pin "145") (pinfunction "145_145") (pintype "passive"))
      (node (ref "P1") (pin "146") (pinfunction "146_146") (pintype "passive"))
      (node (ref "P1") (pin "151") (pinfunction "151_151") (pintype "passive"))
      (node (ref "P1") (pin "152") (pinfunction "152_152") (pintype "passive"))
      (node (ref "P1") (pin "157") (pinfunction "157_157") (pintype "passive"))
      (node (ref "P1") (pin "163") (pinfunction "163_163") (pintype "passive"))
      (node (ref "P1") (pin "164") (pinfunction "164_164") (pintype "passive"))
      (node (ref "P1") (pin "169") (pinfunction "169_169") (pintype "passive"))
      (node (ref "P1") (pin "170") (pinfunction "170_170") (pintype "passive"))
      (node (ref "P1") (pin "181") (pinfunction "181_181") (pintype "passive"))
      (node (ref "P1") (pin "182") (pinfunction "182_182") (pintype "passive"))
      (node (ref "P1") (pin "187") (pinfunction "187_187") (pintype "passive"))
      (node (ref "P1") (pin "188") (pinfunction "188_188") (pintype "passive"))
      (node (ref "P1") (pin "19") (pinfunction "19_19") (pintype "passive"))
      (node (ref "P1") (pin "195") (pinfunction "195_195") (pintype "passive"))
      (node (ref "P1") (pin "196") (pinfunction "196_196") (pintype "passive"))
      (node (ref "P1") (pin "20") (pinfunction "20_20") (pintype "passive"))
      (node (ref "P1") (pin "25") (pinfunction "25_25") (pintype "passive"))
      (node (ref "P1") (pin "26") (pinfunction "26_26") (pintype "passive"))
      (node (ref "P1") (pin "31") (pinfunction "31_31") (pintype "passive"))
      (node (ref "P1") (pin "32") (pinfunction "32_32") (pintype "passive"))
      (node (ref "P1") (pin "37") (pinfunction "37_37") (pintype "passive"))
      (node (ref "P1") (pin "38") (pinfunction "38_38") (pintype "passive"))
      (node (ref "P1") (pin "43") (pinfunction "43_43") (pintype "passive"))
      (node (ref "P1") (pin "44") (pinfunction "44_44") (pintype "passive"))
      (node (ref "P1") (pin "49") (pinfunction "49_49") (pintype "passive"))
      (node (ref "P1") (pin "50") (pinfunction "50_50") (pintype "passive"))
      (node (ref "P1") (pin "55") (pinfunction "55_55") (pintype "passive"))
      (node (ref "P1") (pin "56") (pinfunction "56_56") (pintype "passive"))
      (node (ref "P1") (pin "61") (pinfunction "61_61") (pintype "passive"))
      (node (ref "P1") (pin "62") (pinfunction "62_62") (pintype "passive"))
      (node (ref "P1") (pin "67") (pinfunction "67_67") (pintype "passive"))
      (node (ref "P1") (pin "68") (pinfunction "68_68") (pintype "passive"))
      (node (ref "P1") (pin "7") (pinfunction "7_7") (pintype "passive"))
      (node (ref "P1") (pin "73") (pinfunction "73_73") (pintype "passive"))
      (node (ref "P1") (pin "74") (pinfunction "74_74") (pintype "passive"))
      (node (ref "P1") (pin "79") (pinfunction "79_79") (pintype "passive"))
      (node (ref "P1") (pin "8") (pinfunction "8_8") (pintype "passive"))
      (node (ref "P1") (pin "80") (pinfunction "80_80") (pintype "passive"))
      (node (ref "P1") (pin "85") (pinfunction "85_85") (pintype "passive"))
      (node (ref "P1") (pin "86") (pinfunction "86_86") (pintype "passive"))
      (node (ref "P1") (pin "91") (pinfunction "91_91") (pintype "passive"))
      (node (ref "P1") (pin "92") (pinfunction "92_92") (pintype "passive"))
      (node (ref "P1") (pin "97") (pinfunction "97_97") (pintype "passive"))
      (node (ref "P1") (pin "98") (pinfunction "98_98") (pintype "passive"))
      (node (ref "PROXIMITYSENSOR") (pin "1") (pinfunction "1_1") (pintype "passive"))
      (node (ref "R12") (pin "1") (pinfunction "1_1") (pintype "passive"))
      (node (ref "R13") (pin "2") (pinfunction "2_2") (pintype "passive"))
      (node (ref "R14") (pin "1") (pinfunction "1_1") (pintype "passive"))
      (node (ref "R15") (pin "2") (pinfunction "2_2") (pintype "passive"))
      (node (ref "R16") (pin "1") (pinfunction "1_1") (pintype "passive"))
      (node (ref "R17") (pin "1") (pinfunction "1_1") (pintype "passive"))
      (node (ref "R18") (pin "1") (pinfunction "1_1") (pintype "passive"))
      (node (ref "R19") (pin "1") (pinfunction "1_1") (pintype "passive"))
      (node (ref "R2") (pin "2") (pinfunction "2_2") (pintype "passive"))
      (node (ref "R20") (pin "1") (pinfunction "1_1") (pintype "passive"))
      (node (ref "R21") (pin "1") (pinfunction "1_1") (pintype "passive"))
      (node (ref "R5") (pin "2") (pinfunction "2_2") (pintype "passive"))
      (node (ref "R8") (pin "1") (pinfunction "1_1") (pintype "passive"))
      (node (ref "R9") (pin "2") (pinfunction "2_2") (pintype "passive"))
      (node (ref "S1") (pin "1") (pinfunction "1_1") (pintype "passive"))
      (node (ref "U$1") (pin "1") (pinfunction "PGND_1") (pintype "passive"))
      (node (ref "U$1") (pin "10") (pinfunction "PGND_2_10") (pintype "passive"))
      (node (ref "U$1") (pin "11") (pinfunction "PGND_3_11") (pintype "passive"))
      (node (ref "U$1") (pin "20") (pinfunction "PGND_4_20") (pintype "passive"))
      (node (ref "U$1") (pin "7") (pinfunction "SGND_7") (pintype "passive"))
      (node (ref "U$1") (pin "P$1") (pinfunction "P$1_P$1") (pintype "passive"))
      (node (ref "U$1") (pin "P$2") (pinfunction "P$2_P$2") (pintype "passive"))
      (node (ref "U$1") (pin "P$3") (pinfunction "P$3_P$3") (pintype "passive"))
      (node (ref "U$1") (pin "P$4") (pinfunction "P$4_P$4") (pintype "passive"))
      (node (ref "U$1") (pin "P$5") (pinfunction "P$5_P$5") (pintype "passive"))
      (node (ref "U$1") (pin "P$6") (pinfunction "P$6_P$6") (pintype "passive"))
      (node (ref "U$1") (pin "P$7") (pinfunction "P$7_P$7") (pintype "passive"))
      (node (ref "U$1") (pin "P$8") (pinfunction "P$8_P$8") (pintype "passive"))
      (node (ref "U$1") (pin "P$9") (pinfunction "P$9_P$9") (pintype "passive"))
      (node (ref "U1") (pin "20") (pinfunction "GND_20") (pintype "power_in"))
      (node (ref "U1") (pin "EPAD") (pinfunction "EPAD_EPAD") (pintype "passive"))
      (node (ref "X2") (pin "4") (pinfunction "GND_4") (pintype "power_in"))
    )
    (net (code "37") (name "Net-(C18-Pad1)") (class "Default")
      (node (ref "C18") (pin "1") (pinfunction "1_1") (pintype "passive"))
      (node (ref "R6") (pin "1") (pinfunction "1_1") (pintype "passive"))
    )
    (net (code "38") (name "Net-(C20-Pad2)") (class "Default")
      (node (ref "C20") (pin "2") (pinfunction "2_2") (pintype "passive"))
      (node (ref "R7") (pin "2") (pinfunction "2_2") (pintype "passive"))
    )
    (net (code "39") (name "Net-(D1-PadC)") (class "Default")
      (node (ref "D1") (pin "C") (pinfunction "C_C") (pintype "passive"))
      (node (ref "R18") (pin "2") (pinfunction "2_2") (pintype "passive"))
    )
    (net (code "40") (name "Net-(D2-PadC)") (class "Default")
      (node (ref "D2") (pin "C") (pinfunction "C_C") (pintype "passive"))
      (node (ref "R21") (pin "2") (pinfunction "2_2") (pintype "passive"))
    )
    (net (code "41") (name "Net-(D3-PadC)") (class "Default")
      (node (ref "D3") (pin "C") (pinfunction "C_C") (pintype "passive"))
      (node (ref "R20") (pin "2") (pinfunction "2_2") (pintype "passive"))
    )
    (net (code "42") (name "Net-(D4-PadC)") (class "Default")
      (node (ref "D4") (pin "C") (pinfunction "C_C") (pintype "passive"))
      (node (ref "R19") (pin "2") (pinfunction "2_2") (pintype "passive"))
    )
    (net (code "43") (name "Net-(D5-PadC)") (class "Default")
      (node (ref "D5") (pin "C") (pinfunction "C_C") (pintype "passive"))
      (node (ref "R17") (pin "2") (pinfunction "2_2") (pintype "passive"))
    )
    (net (code "44") (name "Net-(D6-PadC)") (class "Default")
      (node (ref "D6") (pin "C") (pinfunction "C_C") (pintype "passive"))
      (node (ref "R16") (pin "2") (pinfunction "2_2") (pintype "passive"))
    )
    (net (code "45") (name "Net-(IC1-VCAP_1)") (class "Default")
      (node (ref "C16") (pin "1") (pinfunction "1_1") (pintype "passive"))
      (node (ref "IC1") (pin "71") (pinfunction "VCAP_1_71") (pintype "bidirectional"))
    )
    (net (code "46") (name "Net-(IC1-VCAP_2)") (class "Default")
      (node (ref "C17") (pin "1") (pinfunction "1_1") (pintype "passive"))
      (node (ref "IC1") (pin "106") (pinfunction "VCAP_2_106") (pintype "bidirectional"))
    )
    (net (code "47") (name "Net-(IC2-ISET)") (class "Default")
      (node (ref "IC2") (pin "4") (pinfunction "ISET_4") (pintype "input"))
      (node (ref "R12") (pin "2") (pinfunction "2_2") (pintype "passive"))
    )
    (net (code "48") (name "Net-(IC3-ISET)") (class "Default")
      (node (ref "IC3") (pin "4") (pinfunction "ISET_4") (pintype "input"))
      (node (ref "R14") (pin "2") (pinfunction "2_2") (pintype "passive"))
    )
    (net (code "49") (name "Net-(U$1-BURST)") (class "Default")
      (node (ref "R9") (pin "1") (pinfunction "1_1") (pintype "passive"))
      (node (ref "U$1") (pin "8") (pinfunction "BURST_8") (pintype "passive"))
    )
    (net (code "50") (name "Net-(U$1-FB)") (class "Default")
      (node (ref "C18") (pin "2") (pinfunction "2_2") (pintype "passive"))
      (node (ref "C19") (pin "2") (pinfunction "2_2") (pintype "passive"))
      (node (ref "C20") (pin "1") (pinfunction "1_1") (pintype "passive"))
      (node (ref "R4") (pin "2") (pinfunction "2_2") (pintype "passive"))
      (node (ref "R5") (pin "1") (pinfunction "1_1") (pintype "passive"))
      (node (ref "U$1") (pin "13") (pinfunction "FB_13") (pintype "passive"))
    )
    (net (code "51") (name "Net-(U$1-RT)") (class "Default")
      (node (ref "R8") (pin "2") (pinfunction "2_2") (pintype "passive"))
      (node (ref "U$1") (pin "9") (pinfunction "RT_9") (pintype "passive"))
    )
    (net (code "52") (name "Net-(U$1-SW1-Pad15)") (class "Default")
      (node (ref "U$1") (pin "15") (pinfunction "SW1_15") (pintype "passive"))
      (node (ref "U$1") (pin "16") (pinfunction "SW1_16") (pintype "passive"))
      (node (ref "U$1") (pin "17") (pinfunction "SW1_17") (pintype "passive"))
      (node (ref "U$2") (pin "2") (pinfunction "2_2") (pintype "passive"))
    )
    (net (code "53") (name "Net-(U$1-SW2-Pad18)") (class "Default")
      (node (ref "U$1") (pin "18") (pinfunction "SW2_18") (pintype "passive"))
      (node (ref "U$1") (pin "19") (pinfunction "SW2_19") (pintype "passive"))
      (node (ref "U$2") (pin "1") (pinfunction "1_1") (pintype "passive"))
    )
    (net (code "54") (name "Net-(U$1-VC)") (class "Default")
      (node (ref "C19") (pin "1") (pinfunction "1_1") (pintype "passive"))
      (node (ref "R6") (pin "2") (pinfunction "2_2") (pintype "passive"))
      (node (ref "U$1") (pin "12") (pinfunction "VC_12") (pintype "passive"))
    )
    (net (code "55") (name "unconnected-(FTDI-Pad2)") (class "Default")
      (node (ref "FTDI") (pin "2") (pinfunction "2_2") (pintype "passive"))
    )
    (net (code "56") (name "unconnected-(FTDI-Pad6)") (class "Default")
      (node (ref "FTDI") (pin "6") (pinfunction "6_6") (pintype "passive"))
    )
    (net (code "57") (name "unconnected-(IC1-BOOTO-Pad138)") (class "Default")
      (node (ref "IC1") (pin "138") (pinfunction "BOOTO_138") (pintype "bidirectional"))
    )
    (net (code "58") (name "unconnected-(IC1-PA1-Pad35)") (class "Default")
      (node (ref "IC1") (pin "35") (pinfunction "PA1_35") (pintype "bidirectional"))
    )
    (net (code "59") (name "unconnected-(IC1-PA2-Pad36)") (class "Default")
      (node (ref "IC1") (pin "36") (pinfunction "PA2_36") (pintype "bidirectional"))
    )
    (net (code "60") (name "unconnected-(IC1-PA3-Pad37)") (class "Default")
      (node (ref "IC1") (pin "37") (pinfunction "PA3_37") (pintype "bidirectional"))
    )
    (net (code "61") (name "unconnected-(IC1-PA4-Pad40)") (class "Default")
      (node (ref "IC1") (pin "40") (pinfunction "PA4_40") (pintype "bidirectional"))
    )
    (net (code "62") (name "unconnected-(IC1-PA5-Pad41)") (class "Default")
      (node (ref "IC1") (pin "41") (pinfunction "PA5_41") (pintype "bidirectional"))
    )
    (net (code "63") (name "unconnected-(IC1-PA6-Pad42)") (class "Default")
      (node (ref "IC1") (pin "42") (pinfunction "PA6_42") (pintype "bidirectional"))
    )
    (net (code "64") (name "unconnected-(IC1-PA7-Pad43)") (class "Default")
      (node (ref "IC1") (pin "43") (pinfunction "PA7_43") (pintype "bidirectional"))
    )
    (net (code "65") (name "unconnected-(IC1-PA8-Pad100)") (class "Default")
      (node (ref "IC1") (pin "100") (pinfunction "PA8_100") (pintype "bidirectional"))
    )
    (net (code "66") (name "unconnected-(IC1-PA11-Pad103)") (class "Default")
      (node (ref "IC1") (pin "103") (pinfunction "PA11_103") (pintype "bidirectional"))
    )
    (net (code "67") (name "unconnected-(IC1-PA12-Pad104)") (class "Default")
      (node (ref "IC1") (pin "104") (pinfunction "PA12_104") (pintype "bidirectional"))
    )
    (net (code "68") (name "unconnected-(IC1-PA15-Pad110)") (class "Default")
      (node (ref "IC1") (pin "110") (pinfunction "PA15_110") (pintype "bidirectional"))
    )
    (net (code "69") (name "unconnected-(IC1-PAO-Pad34)") (class "Default")
      (node (ref "IC1") (pin "34") (pinfunction "PAO_34") (pintype "bidirectional"))
    )
    (net (code "70") (name "unconnected-(IC1-PB4-Pad134)") (class "Default")
      (node (ref "IC1") (pin "134") (pinfunction "PB4_134") (pintype "bidirectional"))
    )
    (net (code "71") (name "unconnected-(IC1-PB5-Pad135)") (class "Default")
      (node (ref "IC1") (pin "135") (pinfunction "PB5_135") (pintype "bidirectional"))
    )
    (net (code "72") (name "unconnected-(IC1-PB6-Pad136)") (class "Default")
      (node (ref "IC1") (pin "136") (pinfunction "PB6_136") (pintype "bidirectional"))
    )
    (net (code "73") (name "unconnected-(IC1-PB7-Pad137)") (class "Default")
      (node (ref "IC1") (pin "137") (pinfunction "PB7_137") (pintype "bidirectional"))
    )
    (net (code "74") (name "unconnected-(IC1-PB8-Pad139)") (class "Default")
      (node (ref "IC1") (pin "139") (pinfunction "PB8_139") (pintype "bidirectional"))
    )
    (net (code "75") (name "unconnected-(IC1-PB9-Pad140)") (class "Default")
      (node (ref "IC1") (pin "140") (pinfunction "PB9_140") (pintype "bidirectional"))
    )
    (net (code "76") (name "unconnected-(IC1-PB10-Pad69)") (class "Default")
      (node (ref "IC1") (pin "69") (pinfunction "PB10_69") (pintype "bidirectional"))
    )
    (net (code "77") (name "unconnected-(IC1-PB11-Pad70)") (class "Default")
      (node (ref "IC1") (pin "70") (pinfunction "PB11_70") (pintype "bidirectional"))
    )
    (net (code "78") (name "unconnected-(IC1-PB12-Pad73)") (class "Default")
      (node (ref "IC1") (pin "73") (pinfunction "PB12_73") (pintype "bidirectional"))
    )
    (net (code "79") (name "unconnected-(IC1-PB13-Pad74)") (class "Default")
      (node (ref "IC1") (pin "74") (pinfunction "PB13_74") (pintype "bidirectional"))
    )
    (net (code "80") (name "unconnected-(IC1-PB14-Pad75)") (class "Default")
      (node (ref "IC1") (pin "75") (pinfunction "PB14_75") (pintype "bidirectional"))
    )
    (net (code "81") (name "unconnected-(IC1-PB15-Pad76)") (class "Default")
      (node (ref "IC1") (pin "76") (pinfunction "PB15_76") (pintype "bidirectional"))
    )
    (net (code "82") (name "unconnected-(IC1-PBO-Pad46)") (class "Default")
      (node (ref "IC1") (pin "46") (pinfunction "PBO_46") (pintype "bidirectional"))
    )
    (net (code "83") (name "unconnected-(IC1-PC1-Pad27)") (class "Default")
      (node (ref "IC1") (pin "27") (pinfunction "PC1_27") (pintype "bidirectional"))
    )
    (net (code "84") (name "unconnected-(IC1-PC2-Pad28)") (class "Default")
      (node (ref "IC1") (pin "28") (pinfunction "PC2_28") (pintype "bidirectional"))
    )
    (net (code "85") (name "unconnected-(IC1-PC3-Pad29)") (class "Default")
      (node (ref "IC1") (pin "29") (pinfunction "PC3_29") (pintype "bidirectional"))
    )
    (net (code "86") (name "unconnected-(IC1-PC4-Pad44)") (class "Default")
      (node (ref "IC1") (pin "44") (pinfunction "PC4_44") (pintype "bidirectional"))
    )
    (net (code "87") (name "unconnected-(IC1-PC5-Pad45)") (class "Default")
      (node (ref "IC1") (pin "45") (pinfunction "PC5_45") (pintype "bidirectional"))
    )
    (net (code "88") (name "unconnected-(IC1-PC6-Pad96)") (class "Default")
      (node (ref "IC1") (pin "96") (pinfunction "PC6_96") (pintype "bidirectional"))
    )
    (net (code "89") (name "unconnected-(IC1-PC7-Pad97)") (class "Default")
      (node (ref "IC1") (pin "97") (pinfunction "PC7_97") (pintype "bidirectional"))
    )
    (net (code "90") (name "unconnected-(IC1-PC8-Pad98)") (class "Default")
      (node (ref "IC1") (pin "98") (pinfunction "PC8_98") (pintype "bidirectional"))
    )
    (net (code "91") (name "unconnected-(IC1-PC9-Pad99)") (class "Default")
      (node (ref "IC1") (pin "99") (pinfunction "PC9_99") (pintype "bidirectional"))
    )
    (net (code "92") (name "unconnected-(IC1-PC10-Pad111)") (class "Default")
      (node (ref "IC1") (pin "111") (pinfunction "PC10_111") (pintype "bidirectional"))
    )
    (net (code "93") (name "unconnected-(IC1-PC13-Pad7)") (class "Default")
      (node (ref "IC1") (pin "7") (pinfunction "PC13_7") (pintype "bidirectional"))
    )
    (net (code "94") (name "unconnected-(IC1-PC14-Pad8)") (class "Default")
      (node (ref "IC1") (pin "8") (pinfunction "PC14_8") (pintype "bidirectional"))
    )
    (net (code "95") (name "unconnected-(IC1-PC15-Pad9)") (class "Default")
      (node (ref "IC1") (pin "9") (pinfunction "PC15_9") (pintype "bidirectional"))
    )
    (net (code "96") (name "unconnected-(IC1-PCO-Pad26)") (class "Default")
      (node (ref "IC1") (pin "26") (pinfunction "PCO_26") (pintype "bidirectional"))
    )
    (net (code "97") (name "unconnected-(IC1-PD1-Pad115)") (class "Default")
      (node (ref "IC1") (pin "115") (pinfunction "PD1_115") (pintype "bidirectional"))
    )
    (net (code "98") (name "unconnected-(IC1-PD3-Pad117)") (class "Default")
      (node (ref "IC1") (pin "117") (pinfunction "PD3_117") (pintype "bidirectional"))
    )
    (net (code "99") (name "unconnected-(IC1-PD4-Pad118)") (class "Default")
      (node (ref "IC1") (pin "118") (pinfunction "PD4_118") (pintype "bidirectional"))
    )
    (net (code "100") (name "unconnected-(IC1-PD5-Pad119)") (class "Default")
      (node (ref "IC1") (pin "119") (pinfunction "PD5_119") (pintype "bidirectional"))
    )
    (net (code "101") (name "unconnected-(IC1-PD6-Pad122)") (class "Default")
      (node (ref "IC1") (pin "122") (pinfunction "PD6_122") (pintype "bidirectional"))
    )
    (net (code "102") (name "unconnected-(IC1-PD7-Pad123)") (class "Default")
      (node (ref "IC1") (pin "123") (pinfunction "PD7_123") (pintype "bidirectional"))
    )
    (net (code "103") (name "unconnected-(IC1-PD8-Pad77)") (class "Default")
      (node (ref "IC1") (pin "77") (pinfunction "PD8_77") (pintype "bidirectional"))
    )
    (net (code "104") (name "unconnected-(IC1-PD9-Pad78)") (class "Default")
      (node (ref "IC1") (pin "78") (pinfunction "PD9_78") (pintype "bidirectional"))
    )
    (net (code "105") (name "unconnected-(IC1-PD10-Pad79)") (class "Default")
      (node (ref "IC1") (pin "79") (pinfunction "PD10_79") (pintype "bidirectional"))
    )
    (net (code "106") (name "unconnected-(IC1-PD11-Pad80)") (class "Default")
      (node (ref "IC1") (pin "80") (pinfunction "PD11_80") (pintype "bidirectional"))
    )
    (net (code "107") (name "unconnected-(IC1-PD12-Pad81)") (class "Default")
      (node (ref "IC1") (pin "81") (pinfunction "PD12_81") (pintype "bidirectional"))
    )
    (net (code "108") (name "unconnected-(IC1-PD13-Pad82)") (class "Default")
      (node (ref "IC1") (pin "82") (pinfunction "PD13_82") (pintype "bidirectional"))
    )
    (net (code "109") (name "unconnected-(IC1-PD14-Pad85)") (class "Default")
      (node (ref "IC1") (pin "85") (pinfunction "PD14_85") (pintype "bidirectional"))
    )
    (net (code "110") (name "unconnected-(IC1-PD15-Pad86)") (class "Default")
      (node (ref "IC1") (pin "86") (pinfunction "PD15_86") (pintype "bidirectional"))
    )
    (net (code "111") (name "unconnected-(IC1-PDO-Pad114)") (class "Default")
      (node (ref "IC1") (pin "114") (pinfunction "PDO_114") (pintype "bidirectional"))
    )
    (net (code "112") (name "unconnected-(IC1-PDR_ON-Pad143)") (class "Default")
      (node (ref "IC1") (pin "143") (pinfunction "PDR_ON_143") (pintype "bidirectional"))
    )
    (net (code "113") (name "unconnected-(IC1-PE5-Pad4)") (class "Default")
      (node (ref "IC1") (pin "4") (pinfunction "PE5_4") (pintype "bidirectional"))
    )
    (net (code "114") (name "unconnected-(IC1-PE11-Pad64)") (class "Default")
      (node (ref "IC1") (pin "64") (pinfunction "PE11_64") (pintype "bidirectional"))
    )
    (net (code "115") (name "unconnected-(IC1-PE12-Pad65)") (class "Default")
      (node (ref "IC1") (pin "65") (pinfunction "PE12_65") (pintype "bidirectional"))
    )
    (net (code "116") (name "unconnected-(IC1-PE13-Pad66)") (class "Default")
      (node (ref "IC1") (pin "66") (pinfunction "PE13_66") (pintype "bidirectional"))
    )
    (net (code "117") (name "unconnected-(IC1-PE14-Pad67)") (class "Default")
      (node (ref "IC1") (pin "67") (pinfunction "PE14_67") (pintype "bidirectional"))
    )
    (net (code "118") (name "unconnected-(IC1-PE15-Pad68)") (class "Default")
      (node (ref "IC1") (pin "68") (pinfunction "PE15_68") (pintype "bidirectional"))
    )
    (net (code "119") (name "unconnected-(IC1-PEO-Pad141)") (class "Default")
      (node (ref "IC1") (pin "141") (pinfunction "PEO_141") (pintype "bidirectional"))
    )
    (net (code "120") (name "unconnected-(IC1-PF1-Pad11)") (class "Default")
      (node (ref "IC1") (pin "11") (pinfunction "PF1_11") (pintype "bidirectional"))
    )
    (net (code "121") (name "unconnected-(IC1-PF2-Pad12)") (class "Default")
      (node (ref "IC1") (pin "12") (pinfunction "PF2_12") (pintype "bidirectional"))
    )
    (net (code "122") (name "unconnected-(IC1-PF3-Pad13)") (class "Default")
      (node (ref "IC1") (pin "13") (pinfunction "PF3_13") (pintype "bidirectional"))
    )
    (net (code "123") (name "unconnected-(IC1-PF4-Pad14)") (class "Default")
      (node (ref "IC1") (pin "14") (pinfunction "PF4_14") (pintype "bidirectional"))
    )
    (net (code "124") (name "unconnected-(IC1-PF5-Pad15)") (class "Default")
      (node (ref "IC1") (pin "15") (pinfunction "PF5_15") (pintype "bidirectional"))
    )
    (net (code "125") (name "unconnected-(IC1-PF7-Pad19)") (class "Default")
      (node (ref "IC1") (pin "19") (pinfunction "PF7_19") (pintype "bidirectional"))
    )
    (net (code "126") (name "unconnected-(IC1-PF8-Pad20)") (class "Default")
      (node (ref "IC1") (pin "20") (pinfunction "PF8_20") (pintype "bidirectional"))
    )
    (net (code "127") (name "unconnected-(IC1-PF9-Pad21)") (class "Default")
      (node (ref "IC1") (pin "21") (pinfunction "PF9_21") (pintype "bidirectional"))
    )
    (net (code "128") (name "unconnected-(IC1-PF10-Pad22)") (class "Default")
      (node (ref "IC1") (pin "22") (pinfunction "PF10_22") (pintype "bidirectional"))
    )
    (net (code "129") (name "unconnected-(IC1-PF11-Pad49)") (class "Default")
      (node (ref "IC1") (pin "49") (pinfunction "PF11_49") (pintype "bidirectional"))
    )
    (net (code "130") (name "unconnected-(IC1-PF12-Pad50)") (class "Default")
      (node (ref "IC1") (pin "50") (pinfunction "PF12_50") (pintype "bidirectional"))
    )
    (net (code "131") (name "unconnected-(IC1-PF13-Pad53)") (class "Default")
      (node (ref "IC1") (pin "53") (pinfunction "PF13_53") (pintype "bidirectional"))
    )
    (net (code "132") (name "unconnected-(IC1-PF14-Pad54)") (class "Default")
      (node (ref "IC1") (pin "54") (pinfunction "PF14_54") (pintype "bidirectional"))
    )
    (net (code "133") (name "unconnected-(IC1-PF15-Pad55)") (class "Default")
      (node (ref "IC1") (pin "55") (pinfunction "PF15_55") (pintype "bidirectional"))
    )
    (net (code "134") (name "unconnected-(IC1-PFO-Pad10)") (class "Default")
      (node (ref "IC1") (pin "10") (pinfunction "PFO_10") (pintype "bidirectional"))
    )
    (net (code "135") (name "unconnected-(IC1-PG1-Pad57)") (class "Default")
      (node (ref "IC1") (pin "57") (pinfunction "PG1_57") (pintype "bidirectional"))
    )
    (net (code "136") (name "unconnected-(IC1-PG2-Pad87)") (class "Default")
      (node (ref "IC1") (pin "87") (pinfunction "PG2_87") (pintype "bidirectional"))
    )
    (net (code "137") (name "unconnected-(IC1-PG3-Pad88)") (class "Default")
      (node (ref "IC1") (pin "88") (pinfunction "PG3_88") (pintype "bidirectional"))
    )
    (net (code "138") (name "unconnected-(IC1-PG4-Pad89)") (class "Default")
      (node (ref "IC1") (pin "89") (pinfunction "PG4_89") (pintype "bidirectional"))
    )
    (net (code "139") (name "unconnected-(IC1-PG5-Pad90)") (class "Default")
      (node (ref "IC1") (pin "90") (pinfunction "PG5_90") (pintype "bidirectional"))
    )
    (net (code "140") (name "unconnected-(IC1-PG6-Pad91)") (class "Default")
      (node (ref "IC1") (pin "91") (pinfunction "PG6_91") (pintype "bidirectional"))
    )
    (net (code "141") (name "unconnected-(IC1-PG7-Pad92)") (class "Default")
      (node (ref "IC1") (pin "92") (pinfunction "PG7_92") (pintype "bidirectional"))
    )
    (net (code "142") (name "unconnected-(IC1-PG8-Pad93)") (class "Default")
      (node (ref "IC1") (pin "93") (pinfunction "PG8_93") (pintype "bidirectional"))
    )
    (net (code "143") (name "unconnected-(IC1-PG9-Pad124)") (class "Default")
      (node (ref "IC1") (pin "124") (pinfunction "PG9_124") (pintype "bidirectional"))
    )
    (net (code "144") (name "unconnected-(IC1-PG10-Pad125)") (class "Default")
      (node (ref "IC1") (pin "125") (pinfunction "PG10_125") (pintype "bidirectional"))
    )
    (net (code "145") (name "unconnected-(IC1-PG11-Pad126)") (class "Default")
      (node (ref "IC1") (pin "126") (pinfunction "PG11_126") (pintype "bidirectional"))
    )
    (net (code "146") (name "unconnected-(IC1-PG12-Pad127)") (class "Default")
      (node (ref "IC1") (pin "127") (pinfunction "PG12_127") (pintype "bidirectional"))
    )
    (net (code "147") (name "unconnected-(IC1-PG13-Pad128)") (class "Default")
      (node (ref "IC1") (pin "128") (pinfunction "PG13_128") (pintype "bidirectional"))
    )
    (net (code "148") (name "unconnected-(IC1-PG14-Pad129)") (class "Default")
      (node (ref "IC1") (pin "129") (pinfunction "PG14_129") (pintype "bidirectional"))
    )
    (net (code "149") (name "unconnected-(IC1-PG15-Pad132)") (class "Default")
      (node (ref "IC1") (pin "132") (pinfunction "PG15_132") (pintype "bidirectional"))
    )
    (net (code "150") (name "unconnected-(IC1-PGO-Pad56)") (class "Default")
      (node (ref "IC1") (pin "56") (pinfunction "PGO_56") (pintype "bidirectional"))
    )
    (net (code "151") (name "unconnected-(IC1-VBAT-Pad6)") (class "Default")
      (node (ref "IC1") (pin "6") (pinfunction "VBAT_6") (pintype "bidirectional"))
    )
    (net (code "152") (name "unconnected-(J2-KEY-Pad7)") (class "Default")
      (node (ref "J2") (pin "7") (pinfunction "KEY_7") (pintype "bidirectional"))
    )
    (net (code "153") (name "unconnected-(J2-NC{slash}TDI-Pad8)") (class "Default")
      (node (ref "J2") (pin "8") (pinfunction "NC/TDI_8") (pintype "bidirectional"))
    )
    (net (code "154") (name "unconnected-(LCDCONNECTORB-KL-Pad10)") (class "Default")
      (node (ref "LCDCONNECTOR") (pin "10") (pinfunction "KL_10") (pintype "passive"))
    )
    (net (code "155") (name "unconnected-(LCDCONNECTORE-KL-Pad13)") (class "Default")
      (node (ref "LCDCONNECTOR") (pin "13") (pinfunction "KL_13") (pintype "passive"))
    )
    (net (code "156") (name "unconnected-(LCDCONNECTORF-KL-Pad14)") (class "Default")
      (node (ref "LCDCONNECTOR") (pin "14") (pinfunction "KL_14") (pintype "passive"))
    )
    (net (code "157") (name "unconnected-(LCDCONNECTORG-KL-Pad15)") (class "Default")
      (node (ref "LCDCONNECTOR") (pin "15") (pinfunction "KL_15") (pintype "passive"))
    )
    (net (code "158") (name "unconnected-(LCDCONNECTORH-KL-Pad16)") (class "Default")
      (node (ref "LCDCONNECTOR") (pin "16") (pinfunction "KL_16") (pintype "passive"))
    )
    (net (code "159") (name "unconnected-(LCDCONNECTORR-KL-Pad7)") (class "Default")
      (node (ref "LCDCONNECTOR") (pin "7") (pinfunction "KL_7") (pintype "passive"))
    )
    (net (code "160") (name "unconnected-(LCDCONNECTORT-KL-Pad9)") (class "Default")
      (node (ref "LCDCONNECTOR") (pin "9") (pinfunction "KL_9") (pintype "passive"))
    )
    (net (code "161") (name "unconnected-(P1-Pad2)") (class "Default")
      (node (ref "P1") (pin "2") (pinfunction "2_2") (pintype "passive"))
    )
    (net (code "162") (name "unconnected-(P1-Pad3)") (class "Default")
      (node (ref "P1") (pin "3") (pinfunction "3_3") (pintype "passive"))
    )
    (net (code "163") (name "unconnected-(P1-Pad4)") (class "Default")
      (node (ref "P1") (pin "4") (pinfunction "4_4") (pintype "passive"))
    )
    (net (code "164") (name "unconnected-(P1-Pad5)") (class "Default")
      (node (ref "P1") (pin "5") (pinfunction "5_5") (pintype "passive"))
    )
    (net (code "165") (name "unconnected-(P1-Pad6)") (class "Default")
      (node (ref "P1") (pin "6") (pinfunction "6_6") (pintype "passive"))
    )
    (net (code "166") (name "unconnected-(P1-Pad9)") (class "Default")
      (node (ref "P1") (pin "9") (pinfunction "9_9") (pintype "passive"))
    )
    (net (code "167") (name "unconnected-(P1-Pad10)") (class "Default")
      (node (ref "P1") (pin "10") (pinfunction "10_10") (pintype "passive"))
    )
    (net (code "168") (name "unconnected-(P1-Pad11)") (class "Default")
      (node (ref "P1") (pin "11") (pinfunction "11_11") (pintype "passive"))
    )
    (net (code "169") (name "unconnected-(P1-Pad12)") (class "Default")
      (node (ref "P1") (pin "12") (pinfunction "12_12") (pintype "passive"))
    )
    (net (code "170") (name "unconnected-(P1-Pad15)") (class "Default")
      (node (ref "P1") (pin "15") (pinfunction "15_15") (pintype "passive"))
    )
    (net (code "171") (name "unconnected-(P1-Pad16)") (class "Default")
      (node (ref "P1") (pin "16") (pinfunction "16_16") (pintype "passive"))
    )
    (net (code "172") (name "unconnected-(P1-Pad17)") (class "Default")
      (node (ref "P1") (pin "17") (pinfunction "17_17") (pintype "passive"))
    )
    (net (code "173") (name "unconnected-(P1-Pad18)") (class "Default")
      (node (ref "P1") (pin "18") (pinfunction "18_18") (pintype "passive"))
    )
    (net (code "174") (name "unconnected-(P1-Pad21)") (class "Default")
      (node (ref "P1") (pin "21") (pinfunction "21_21") (pintype "passive"))
    )
    (net (code "175") (name "unconnected-(P1-Pad22)") (class "Default")
      (node (ref "P1") (pin "22") (pinfunction "22_22") (pintype "passive"))
    )
    (net (code "176") (name "unconnected-(P1-Pad23)") (class "Default")
      (node (ref "P1") (pin "23") (pinfunction "23_23") (pintype "passive"))
    )
    (net (code "177") (name "unconnected-(P1-Pad24)") (class "Default")
      (node (ref "P1") (pin "24") (pinfunction "24_24") (pintype "passive"))
    )
    (net (code "178") (name "unconnected-(P1-Pad27)") (class "Default")
      (node (ref "P1") (pin "27") (pinfunction "27_27") (pintype "passive"))
    )
    (net (code "179") (name "unconnected-(P1-Pad28)") (class "Default")
      (node (ref "P1") (pin "28") (pinfunction "28_28") (pintype "passive"))
    )
    (net (code "180") (name "unconnected-(P1-Pad29)") (class "Default")
      (node (ref "P1") (pin "29") (pinfunction "29_29") (pintype "passive"))
    )
    (net (code "181") (name "unconnected-(P1-Pad30)") (class "Default")
      (node (ref "P1") (pin "30") (pinfunction "30_30") (pintype "passive"))
    )
    (net (code "182") (name "unconnected-(P1-Pad33)") (class "Default")
      (node (ref "P1") (pin "33") (pinfunction "33_33") (pintype "passive"))
    )
    (net (code "183") (name "unconnected-(P1-Pad34)") (class "Default")
      (node (ref "P1") (pin "34") (pinfunction "34_34") (pintype "passive"))
    )
    (net (code "184") (name "unconnected-(P1-Pad35)") (class "Default")
      (node (ref "P1") (pin "35") (pinfunction "35_35") (pintype "passive"))
    )
    (net (code "185") (name "unconnected-(P1-Pad36)") (class "Default")
      (node (ref "P1") (pin "36") (pinfunction "36_36") (pintype "passive"))
    )
    (net (code "186") (name "unconnected-(P1-Pad39)") (class "Default")
      (node (ref "P1") (pin "39") (pinfunction "39_39") (pintype "passive"))
    )
    (net (code "187") (name "unconnected-(P1-Pad40)") (class "Default")
      (node (ref "P1") (pin "40") (pinfunction "40_40") (pintype "passive"))
    )
    (net (code "188") (name "unconnected-(P1-Pad41)") (class "Default")
      (node (ref "P1") (pin "41") (pinfunction "41_41") (pintype "passive"))
    )
    (net (code "189") (name "unconnected-(P1-Pad42)") (class "Default")
      (node (ref "P1") (pin "42") (pinfunction "42_42") (pintype "passive"))
    )
    (net (code "190") (name "unconnected-(P1-Pad45)") (class "Default")
      (node (ref "P1") (pin "45") (pinfunction "45_45") (pintype "passive"))
    )
    (net (code "191") (name "unconnected-(P1-Pad46)") (class "Default")
      (node (ref "P1") (pin "46") (pinfunction "46_46") (pintype "passive"))
    )
    (net (code "192") (name "unconnected-(P1-Pad47)") (class "Default")
      (node (ref "P1") (pin "47") (pinfunction "47_47") (pintype "passive"))
    )
    (net (code "193") (name "unconnected-(P1-Pad48)") (class "Default")
      (node (ref "P1") (pin "48") (pinfunction "48_48") (pintype "passive"))
    )
    (net (code "194") (name "unconnected-(P1-Pad52)") (class "Default")
      (node (ref "P1") (pin "52") (pinfunction "52_52") (pintype "passive"))
    )
    (net (code "195") (name "unconnected-(P1-Pad54)") (class "Default")
      (node (ref "P1") (pin "54") (pinfunction "54_54") (pintype "passive"))
    )
    (net (code "196") (name "unconnected-(P1-Pad57)") (class "Default")
      (node (ref "P1") (pin "57") (pinfunction "57_57") (pintype "passive"))
    )
    (net (code "197") (name "unconnected-(P1-Pad58)") (class "Default")
      (node (ref "P1") (pin "58") (pinfunction "58_58") (pintype "passive"))
    )
    (net (code "198") (name "unconnected-(P1-Pad59)") (class "Default")
      (node (ref "P1") (pin "59") (pinfunction "59_59") (pintype "passive"))
    )
    (net (code "199") (name "unconnected-(P1-Pad60)") (class "Default")
      (node (ref "P1") (pin "60") (pinfunction "60_60") (pintype "passive"))
    )
    (net (code "200") (name "unconnected-(P1-Pad63)") (class "Default")
      (node (ref "P1") (pin "63") (pinfunction "63_63") (pintype "passive"))
    )
    (net (code "201") (name "unconnected-(P1-Pad64)") (class "Default")
      (node (ref "P1") (pin "64") (pinfunction "64_64") (pintype "passive"))
    )
    (net (code "202") (name "unconnected-(P1-Pad65)") (class "Default")
      (node (ref "P1") (pin "65") (pinfunction "65_65") (pintype "passive"))
    )
    (net (code "203") (name "unconnected-(P1-Pad66)") (class "Default")
      (node (ref "P1") (pin "66") (pinfunction "66_66") (pintype "passive"))
    )
    (net (code "204") (name "unconnected-(P1-Pad69)") (class "Default")
      (node (ref "P1") (pin "69") (pinfunction "69_69") (pintype "passive"))
    )
    (net (code "205") (name "unconnected-(P1-Pad70)") (class "Default")
      (node (ref "P1") (pin "70") (pinfunction "70_70") (pintype "passive"))
    )
    (net (code "206") (name "unconnected-(P1-Pad71)") (class "Default")
      (node (ref "P1") (pin "71") (pinfunction "71_71") (pintype "passive"))
    )
    (net (code "207") (name "unconnected-(P1-Pad72)") (class "Default")
      (node (ref "P1") (pin "72") (pinfunction "72_72") (pintype "passive"))
    )
    (net (code "208") (name "unconnected-(P1-Pad75)") (class "Default")
      (node (ref "P1") (pin "75") (pinfunction "75_75") (pintype "passive"))
    )
    (net (code "209") (name "unconnected-(P1-Pad76)") (class "Default")
      (node (ref "P1") (pin "76") (pinfunction "76_76") (pintype "passive"))
    )
    (net (code "210") (name "unconnected-(P1-Pad77)") (class "Default")
      (node (ref "P1") (pin "77") (pinfunction "77_77") (pintype "passive"))
    )
    (net (code "211") (name "unconnected-(P1-Pad78)") (class "Default")
      (node (ref "P1") (pin "78") (pinfunction "78_78") (pintype "passive"))
    )
    (net (code "212") (name "unconnected-(P1-Pad81)") (class "Default")
      (node (ref "P1") (pin "81") (pinfunction "81_81") (pintype "passive"))
    )
    (net (code "213") (name "unconnected-(P1-Pad82)") (class "Default")
      (node (ref "P1") (pin "82") (pinfunction "82_82") (pintype "passive"))
    )
    (net (code "214") (name "unconnected-(P1-Pad83)") (class "Default")
      (node (ref "P1") (pin "83") (pinfunction "83_83") (pintype "passive"))
    )
    (net (code "215") (name "unconnected-(P1-Pad84)") (class "Default")
      (node (ref "P1") (pin "84") (pinfunction "84_84") (pintype "passive"))
    )
    (net (code "216") (name "unconnected-(P1-Pad87)") (class "Default")
      (node (ref "P1") (pin "87") (pinfunction "87_87") (pintype "passive"))
    )
    (net (code "217") (name "unconnected-(P1-Pad88)") (class "Default")
      (node (ref "P1") (pin "88") (pinfunction "88_88") (pintype "passive"))
    )
    (net (code "218") (name "unconnected-(P1-Pad89)") (class "Default")
      (node (ref "P1") (pin "89") (pinfunction "89_89") (pintype "passive"))
    )
    (net (code "219") (name "unconnected-(P1-Pad90)") (class "Default")
      (node (ref "P1") (pin "90") (pinfunction "90_90") (pintype "passive"))
    )
    (net (code "220") (name "unconnected-(P1-Pad93)") (class "Default")
      (node (ref "P1") (pin "93") (pinfunction "93_93") (pintype "passive"))
    )
    (net (code "221") (name "unconnected-(P1-Pad94)") (class "Default")
      (node (ref "P1") (pin "94") (pinfunction "94_94") (pintype "passive"))
    )
    (net (code "222") (name "unconnected-(P1-Pad95)") (class "Default")
      (node (ref "P1") (pin "95") (pinfunction "95_95") (pintype "passive"))
    )
    (net (code "223") (name "unconnected-(P1-Pad96)") (class "Default")
      (node (ref "P1") (pin "96") (pinfunction "96_96") (pintype "passive"))
    )
    (net (code "224") (name "unconnected-(P1-Pad99)") (class "Default")
      (node (ref "P1") (pin "99") (pinfunction "99_99") (pintype "passive"))
    )
    (net (code "225") (name "unconnected-(P1-Pad100)") (class "Default")
      (node (ref "P1") (pin "100") (pinfunction "100_100") (pintype "passive"))
    )
    (net (code "226") (name "unconnected-(P1-Pad101)") (class "Default")
      (node (ref "P1") (pin "101") (pinfunction "101_101") (pintype "passive"))
    )
    (net (code "227") (name "unconnected-(P1-Pad102)") (class "Default")
      (node (ref "P1") (pin "102") (pinfunction "102_102") (pintype "passive"))
    )
    (net (code "228") (name "unconnected-(P1-Pad105)") (class "Default")
      (node (ref "P1") (pin "105") (pinfunction "105_105") (pintype "passive"))
    )
    (net (code "229") (name "unconnected-(P1-Pad106)") (class "Default")
      (node (ref "P1") (pin "106") (pinfunction "106_106") (pintype "passive"))
    )
    (net (code "230") (name "unconnected-(P1-Pad107)") (class "Default")
      (node (ref "P1") (pin "107") (pinfunction "107_107") (pintype "passive"))
    )
    (net (code "231") (name "unconnected-(P1-Pad108)") (class "Default")
      (node (ref "P1") (pin "108") (pinfunction "108_108") (pintype "passive"))
    )
    (net (code "232") (name "unconnected-(P1-Pad111)") (class "Default")
      (node (ref "P1") (pin "111") (pinfunction "111_111") (pintype "passive"))
    )
    (net (code "233") (name "unconnected-(P1-Pad112)") (class "Default")
      (node (ref "P1") (pin "112") (pinfunction "112_112") (pintype "passive"))
    )
    (net (code "234") (name "unconnected-(P1-Pad113)") (class "Default")
      (node (ref "P1") (pin "113") (pinfunction "113_113") (pintype "passive"))
    )
    (net (code "235") (name "unconnected-(P1-Pad114)") (class "Default")
      (node (ref "P1") (pin "114") (pinfunction "114_114") (pintype "passive"))
    )
    (net (code "236") (name "unconnected-(P1-Pad117)") (class "Default")
      (node (ref "P1") (pin "117") (pinfunction "117_117") (pintype "passive"))
    )
    (net (code "237") (name "unconnected-(P1-Pad118)") (class "Default")
      (node (ref "P1") (pin "118") (pinfunction "118_118") (pintype "passive"))
    )
    (net (code "238") (name "unconnected-(P1-Pad119)") (class "Default")
      (node (ref "P1") (pin "119") (pinfunction "119_119") (pintype "passive"))
    )
    (net (code "239") (name "unconnected-(P1-Pad120)") (class "Default")
      (node (ref "P1") (pin "120") (pinfunction "120_120") (pintype "passive"))
    )
    (net (code "240") (name "unconnected-(P1-Pad123)") (class "Default")
      (node (ref "P1") (pin "123") (pinfunction "123_123") (pintype "passive"))
    )
    (net (code "241") (name "unconnected-(P1-Pad124)") (class "Default")
      (node (ref "P1") (pin "124") (pinfunction "124_124") (pintype "passive"))
    )
    (net (code "242") (name "unconnected-(P1-Pad125)") (class "Default")
      (node (ref "P1") (pin "125") (pinfunction "125_125") (pintype "passive"))
    )
    (net (code "243") (name "unconnected-(P1-Pad126)") (class "Default")
      (node (ref "P1") (pin "126") (pinfunction "126_126") (pintype "passive"))
    )
    (net (code "244") (name "unconnected-(P1-Pad128)") (class "Default")
      (node (ref "P1") (pin "128") (pinfunction "128_128") (pintype "passive"))
    )
    (net (code "245") (name "unconnected-(P1-Pad129)") (class "Default")
      (node (ref "P1") (pin "129") (pinfunction "129_129") (pintype "passive"))
    )
    (net (code "246") (name "unconnected-(P1-Pad130)") (class "Default")
      (node (ref "P1") (pin "130") (pinfunction "130_130") (pintype "passive"))
    )
    (net (code "247") (name "unconnected-(P1-Pad131)") (class "Default")
      (node (ref "P1") (pin "131") (pinfunction "131_131") (pintype "passive"))
    )
    (net (code "248") (name "unconnected-(P1-Pad132)") (class "Default")
      (node (ref "P1") (pin "132") (pinfunction "132_132") (pintype "passive"))
    )
    (net (code "249") (name "unconnected-(P1-Pad135)") (class "Default")
      (node (ref "P1") (pin "135") (pinfunction "135_135") (pintype "passive"))
    )
    (net (code "250") (name "unconnected-(P1-Pad136)") (class "Default")
      (node (ref "P1") (pin "136") (pinfunction "136_136") (pintype "passive"))
    )
    (net (code "251") (name "unconnected-(P1-Pad137)") (class "Default")
      (node (ref "P1") (pin "137") (pinfunction "137_137") (pintype "passive"))
    )
    (net (code "252") (name "unconnected-(P1-Pad138)") (class "Default")
      (node (ref "P1") (pin "138") (pinfunction "138_138") (pintype "passive"))
    )
    (net (code "253") (name "unconnected-(P1-Pad141)") (class "Default")
      (node (ref "P1") (pin "141") (pinfunction "141_141") (pintype "passive"))
    )
    (net (code "254") (name "unconnected-(P1-Pad142)") (class "Default")
      (node (ref "P1") (pin "142") (pinfunction "142_142") (pintype "passive"))
    )
    (net (code "255") (name "unconnected-(P1-Pad143)") (class "Default")
      (node (ref "P1") (pin "143") (pinfunction "143_143") (pintype "passive"))
    )
    (net (code "256") (name "unconnected-(P1-Pad144)") (class "Default")
      (node (ref "P1") (pin "144") (pinfunction "144_144") (pintype "passive"))
    )
    (net (code "257") (name "unconnected-(P1-Pad147)") (class "Default")
      (node (ref "P1") (pin "147") (pinfunction "147_147") (pintype "passive"))
    )
    (net (code "258") (name "unconnected-(P1-Pad148)") (class "Default")
      (node (ref "P1") (pin "148") (pinfunction "148_148") (pintype "passive"))
    )
    (net (code "259") (name "unconnected-(P1-Pad149)") (class "Default")
      (node (ref "P1") (pin "149") (pinfunction "149_149") (pintype "passive"))
    )
    (net (code "260") (name "unconnected-(P1-Pad150)") (class "Default")
      (node (ref "P1") (pin "150") (pinfunction "150_150") (pintype "passive"))
    )
    (net (code "261") (name "unconnected-(P1-Pad153)") (class "Default")
      (node (ref "P1") (pin "153") (pinfunction "153_153") (pintype "passive"))
    )
    (net (code "262") (name "unconnected-(P1-Pad154)") (class "Default")
      (node (ref "P1") (pin "154") (pinfunction "154_154") (pintype "passive"))
    )
    (net (code "263") (name "unconnected-(P1-Pad155)") (class "Default")
      (node (ref "P1") (pin "155") (pinfunction "155_155") (pintype "passive"))
    )
    (net (code "264") (name "unconnected-(P1-Pad156)") (class "Default")
      (node (ref "P1") (pin "156") (pinfunction "156_156") (pintype "passive"))
    )
    (net (code "265") (name "unconnected-(P1-Pad158)") (class "Default")
      (node (ref "P1") (pin "158") (pinfunction "158_158") (pintype "passive"))
    )
    (net (code "266") (name "unconnected-(P1-Pad159)") (class "Default")
      (node (ref "P1") (pin "159") (pinfunction "159_159") (pintype "passive"))
    )
    (net (code "267") (name "unconnected-(P1-Pad160)") (class "Default")
      (node (ref "P1") (pin "160") (pinfunction "160_160") (pintype "passive"))
    )
    (net (code "268") (name "unconnected-(P1-Pad161)") (class "Default")
      (node (ref "P1") (pin "161") (pinfunction "161_161") (pintype "passive"))
    )
    (net (code "269") (name "unconnected-(P1-Pad162)") (class "Default")
      (node (ref "P1") (pin "162") (pinfunction "162_162") (pintype "passive"))
    )
    (net (code "270") (name "unconnected-(P1-Pad166)") (class "Default")
      (node (ref "P1") (pin "166") (pinfunction "166_166") (pintype "passive"))
    )
    (net (code "271") (name "unconnected-(P1-Pad171)") (class "Default")
      (node (ref "P1") (pin "171") (pinfunction "171_171") (pintype "passive"))
    )
    (net (code "272") (name "unconnected-(P1-Pad172)") (class "Default")
      (node (ref "P1") (pin "172") (pinfunction "172_172") (pintype "passive"))
    )
    (net (code "273") (name "unconnected-(P1-Pad173)") (class "Default")
      (node (ref "P1") (pin "173") (pinfunction "173_173") (pintype "passive"))
    )
    (net (code "274") (name "unconnected-(P1-Pad174)") (class "Default")
      (node (ref "P1") (pin "174") (pinfunction "174_174") (pintype "passive"))
    )
    (net (code "275") (name "unconnected-(P1-Pad175)") (class "Default")
      (node (ref "P1") (pin "175") (pinfunction "175_175") (pintype "passive"))
    )
    (net (code "276") (name "unconnected-(P1-Pad176)") (class "Default")
      (node (ref "P1") (pin "176") (pinfunction "176_176") (pintype "passive"))
    )
    (net (code "277") (name "unconnected-(P1-Pad178)") (class "Default")
      (node (ref "P1") (pin "178") (pinfunction "178_178") (pintype "passive"))
    )
    (net (code "278") (name "unconnected-(P1-Pad179)") (class "Default")
      (node (ref "P1") (pin "179") (pinfunction "179_179") (pintype "passive"))
    )
    (net (code "279") (name "unconnected-(P1-Pad180)") (class "Default")
      (node (ref "P1") (pin "180") (pinfunction "180_180") (pintype "passive"))
    )
    (net (code "280") (name "unconnected-(P1-Pad189)") (class "Default")
      (node (ref "P1") (pin "189") (pinfunction "189_189") (pintype "passive"))
    )
    (net (code "281") (name "unconnected-(P1-Pad190)") (class "Default")
      (node (ref "P1") (pin "190") (pinfunction "190_190") (pintype "passive"))
    )
    (net (code "282") (name "unconnected-(PROXIMITYSENSOR-Pad4)") (class "Default")
      (node (ref "PROXIMITYSENSOR") (pin "4") (pinfunction "4_4") (pintype "passive"))
    )
    (net (code "283") (name "unconnected-(U1B-NC-Pad19)") (class "Default")
      (node (ref "U1") (pin "19") (pinfunction "NC_19") (pintype "passive"))
    )
    (net (code "284") (name "unconnected-(U1B-NC_2-Pad1)") (class "Default")
      (node (ref "U1") (pin "1") (pinfunction "NC_2_1") (pintype "passive"))
    )
    (net (code "285") (name "unconnected-(U1B-NC_3-Pad2)") (class "Default")
      (node (ref "U1") (pin "2") (pinfunction "NC_3_2") (pintype "passive"))
    )
    (net (code "286") (name "unconnected-(U1B-NC_4-Pad3)") (class "Default")
      (node (ref "U1") (pin "3") (pinfunction "NC_4_3") (pintype "passive"))
    )
    (net (code "287") (name "unconnected-(U1B-NC_5-Pad5)") (class "Default")
      (node (ref "U1") (pin "5") (pinfunction "NC_5_5") (pintype "passive"))
    )
    (net (code "288") (name "unconnected-(U1B-NC_6-Pad7)") (class "Default")
      (node (ref "U1") (pin "7") (pinfunction "NC_6_7") (pintype "passive"))
    )
    (net (code "289") (name "unconnected-(U1B-NC_7-Pad9)") (class "Default")
      (node (ref "U1") (pin "9") (pinfunction "NC_7_9") (pintype "passive"))
    )
    (net (code "290") (name "unconnected-(U1B-NC_8-Pad10)") (class "Default")
      (node (ref "U1") (pin "10") (pinfunction "NC_8_10") (pintype "passive"))
    )
    (net (code "291") (name "unconnected-(U1B-NC_9-Pad11)") (class "Default")
      (node (ref "U1") (pin "11") (pinfunction "NC_9_11") (pintype "passive"))
    )
    (net (code "292") (name "unconnected-(U1B-NC_10-Pad12)") (class "Default")
      (node (ref "U1") (pin "12") (pinfunction "NC_10_12") (pintype "passive"))
    )
    (net (code "293") (name "unconnected-(U1B-NC_11-Pad13)") (class "Default")
      (node (ref "U1") (pin "13") (pinfunction "NC_11_13") (pintype "passive"))
    )
    (net (code "294") (name "unconnected-(U1B-NC_12-Pad14)") (class "Default")
      (node (ref "U1") (pin "14") (pinfunction "NC_12_14") (pintype "passive"))
    )
    (net (code "295") (name "unconnected-(U1B-NC_13-Pad15)") (class "Default")
      (node (ref "U1") (pin "15") (pinfunction "NC_13_15") (pintype "passive"))
    )
    (net (code "296") (name "unconnected-(U1B-NC_14-Pad16)") (class "Default")
      (node (ref "U1") (pin "16") (pinfunction "NC_14_16") (pintype "passive"))
    )
    (net (code "297") (name "unconnected-(U1B-NC_15-Pad17)") (class "Default")
      (node (ref "U1") (pin "17") (pinfunction "NC_15_17") (pintype "passive"))
    )
    (net (code "298") (name "unconnected-(U1B-NC_16-Pad18)") (class "Default")
      (node (ref "U1") (pin "18") (pinfunction "NC_16_18") (pintype "passive"))
    )
  )
)
